# kulgurpowerMCU3.net
KiCad netlist of a schematic drawn in EAGLE
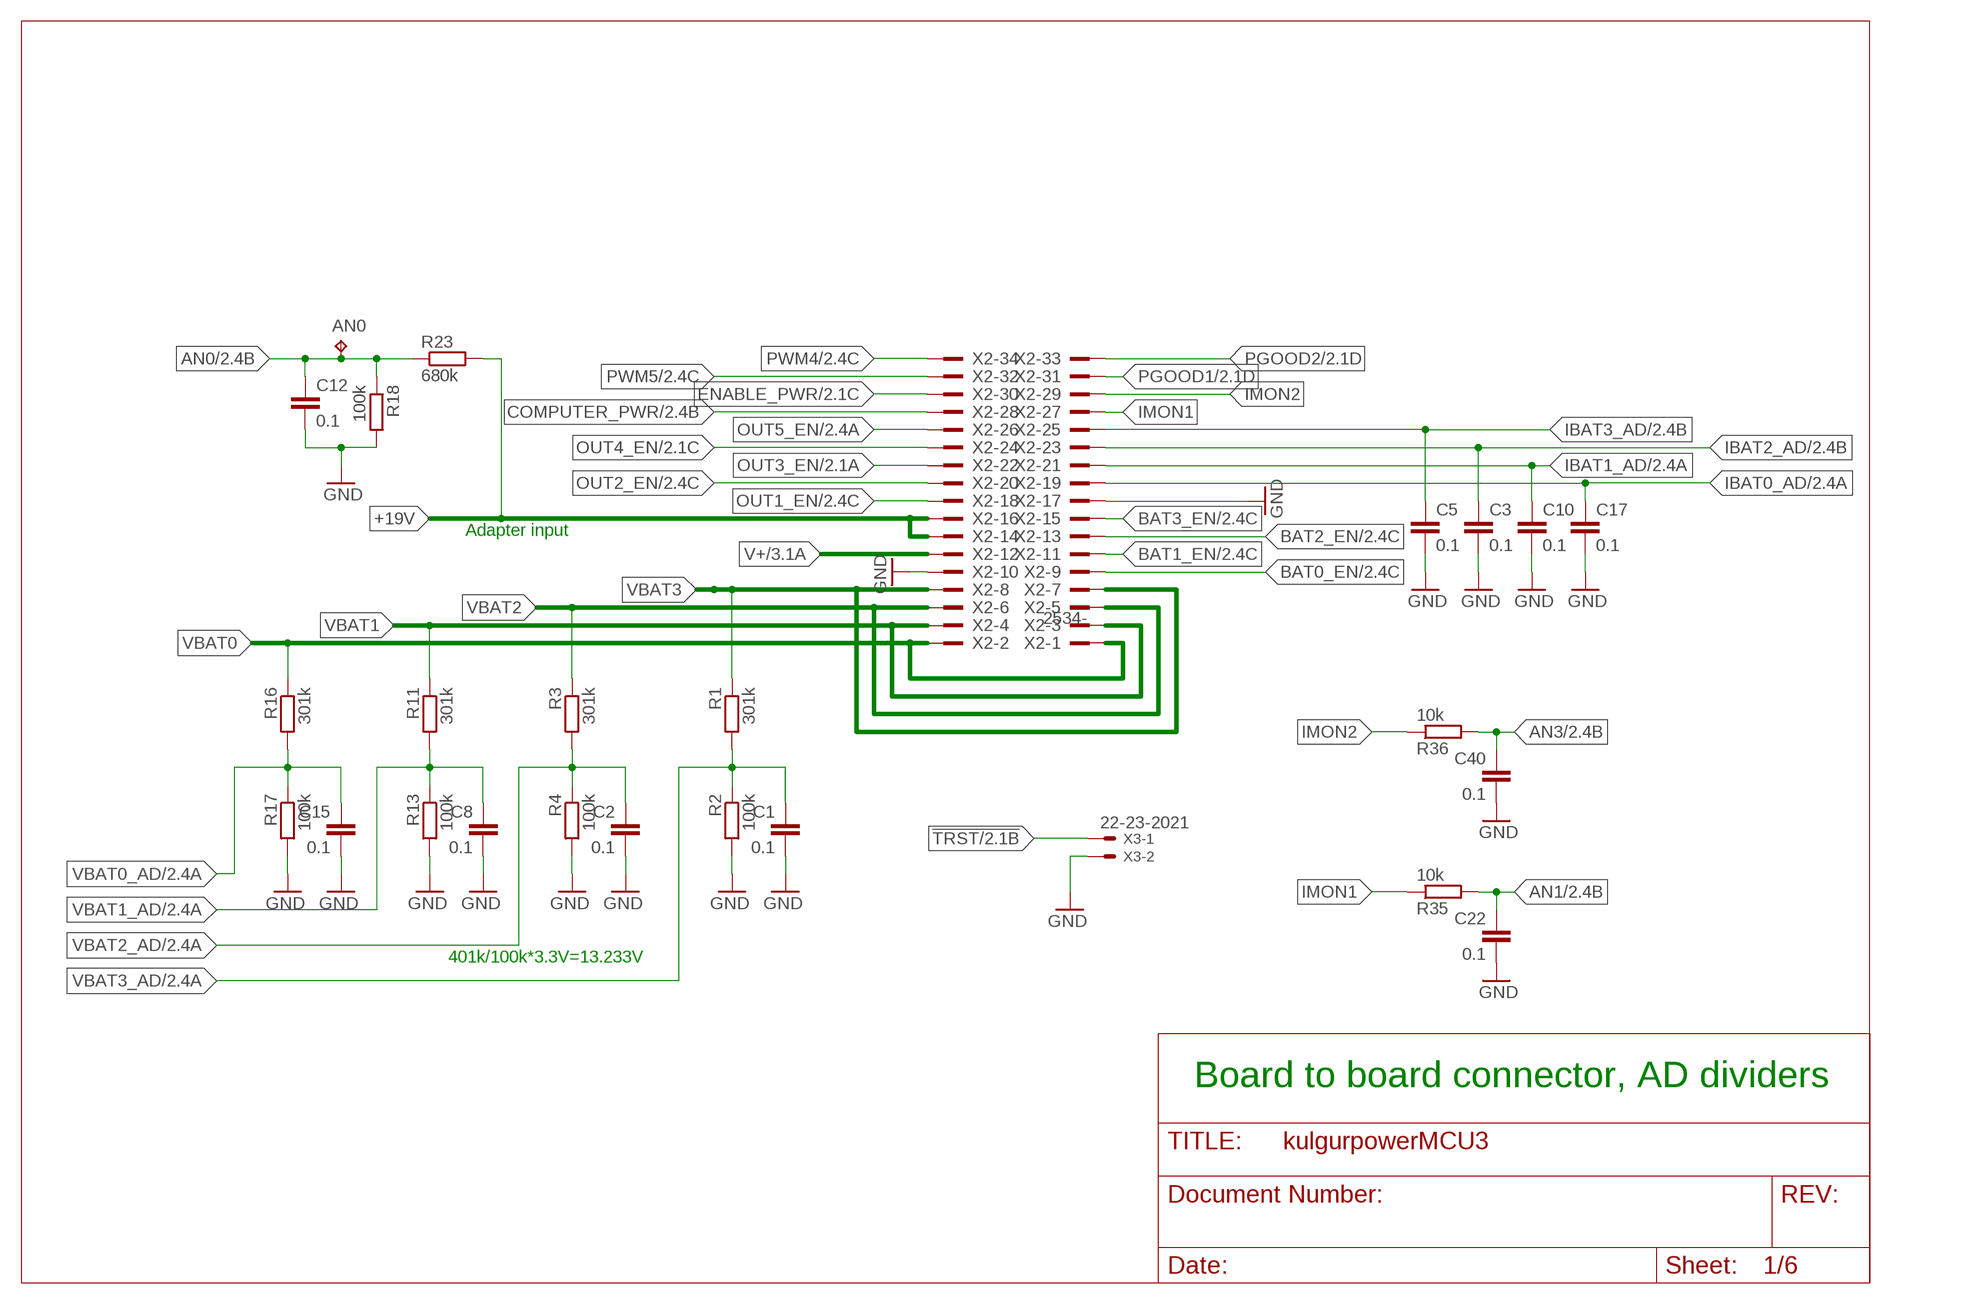
[diagram p0: schematic, sheet 1]
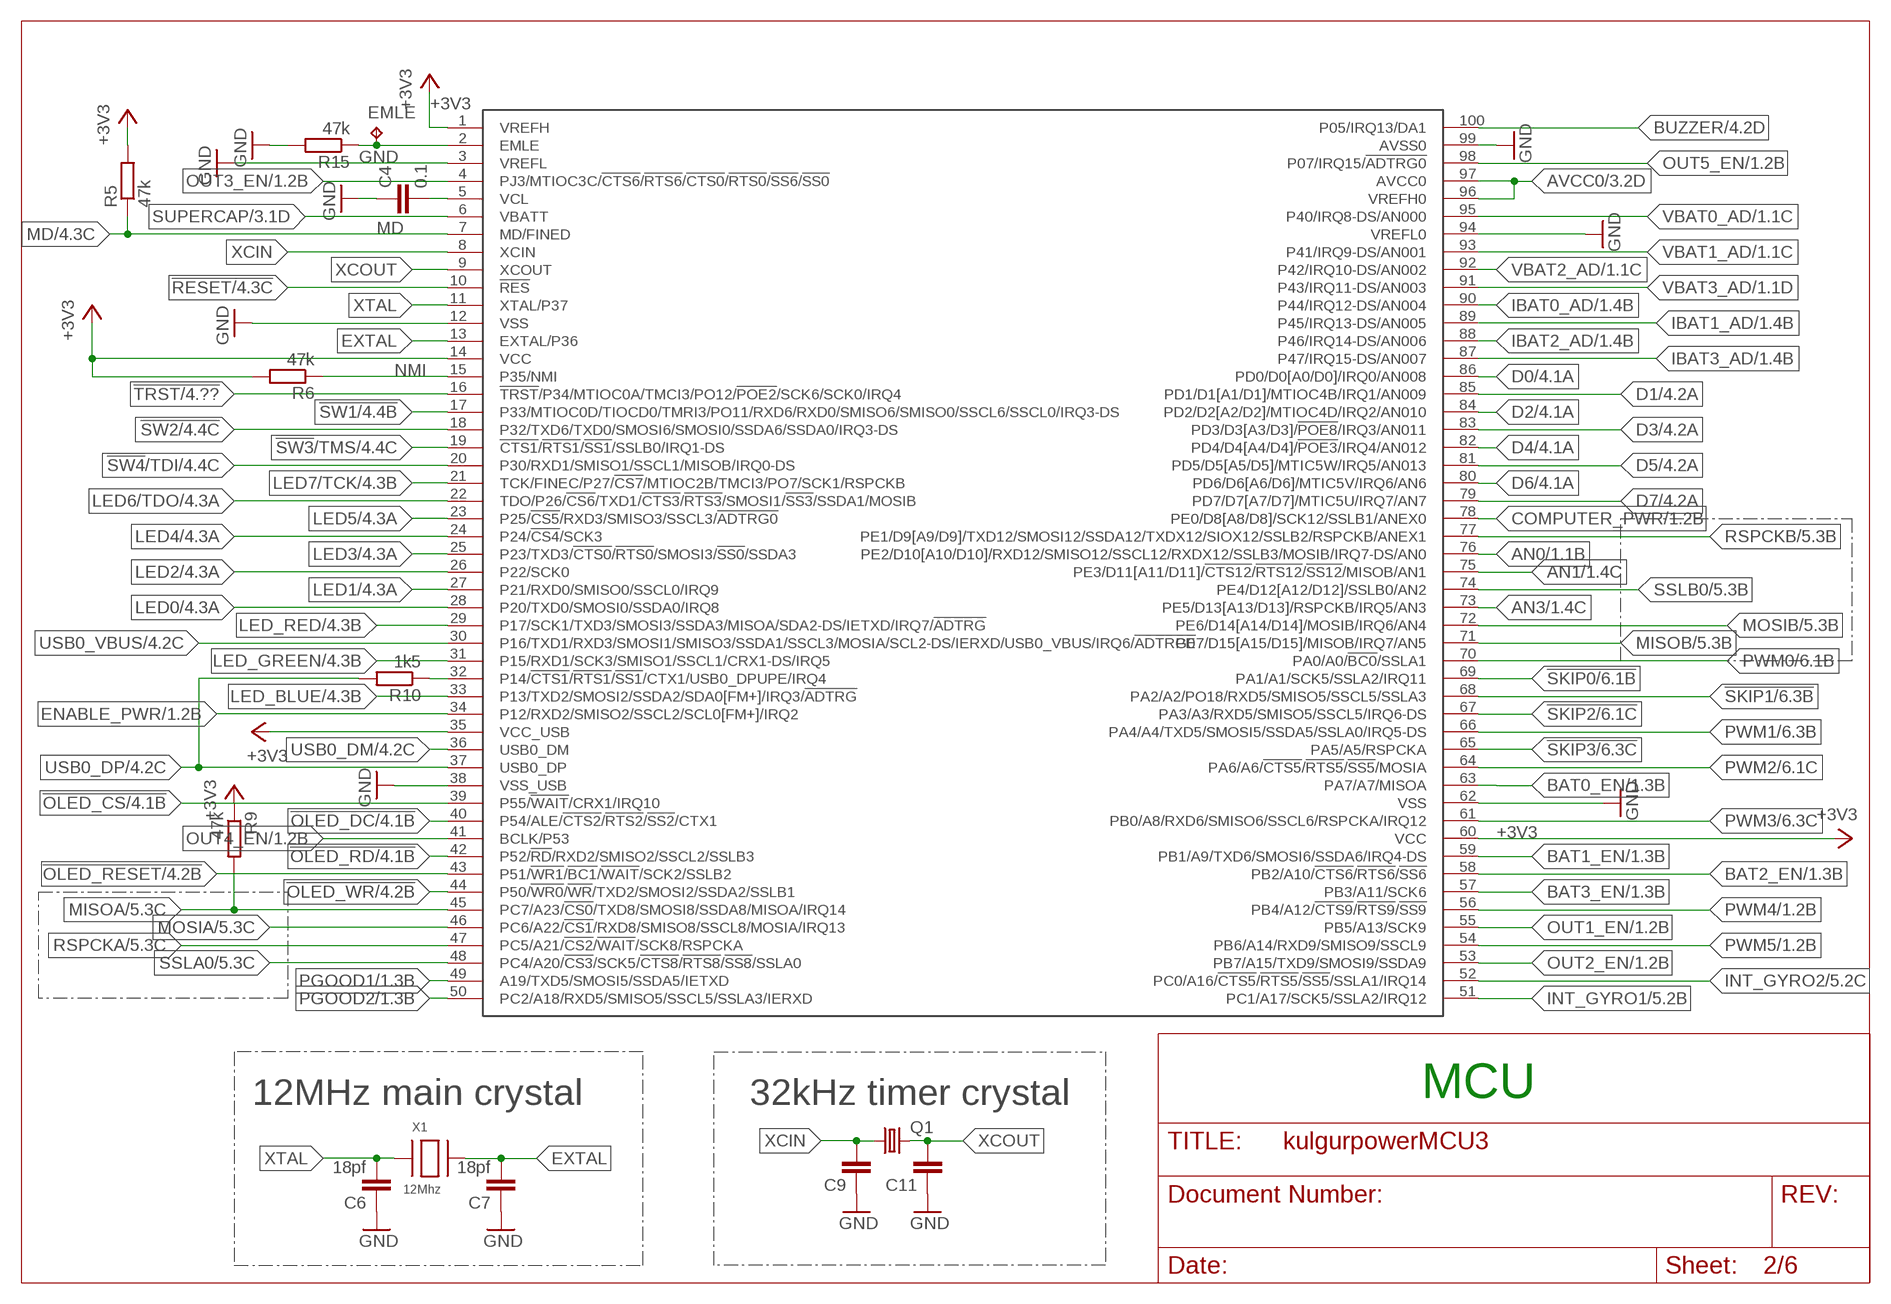
[diagram p1: schematic, sheet 2]
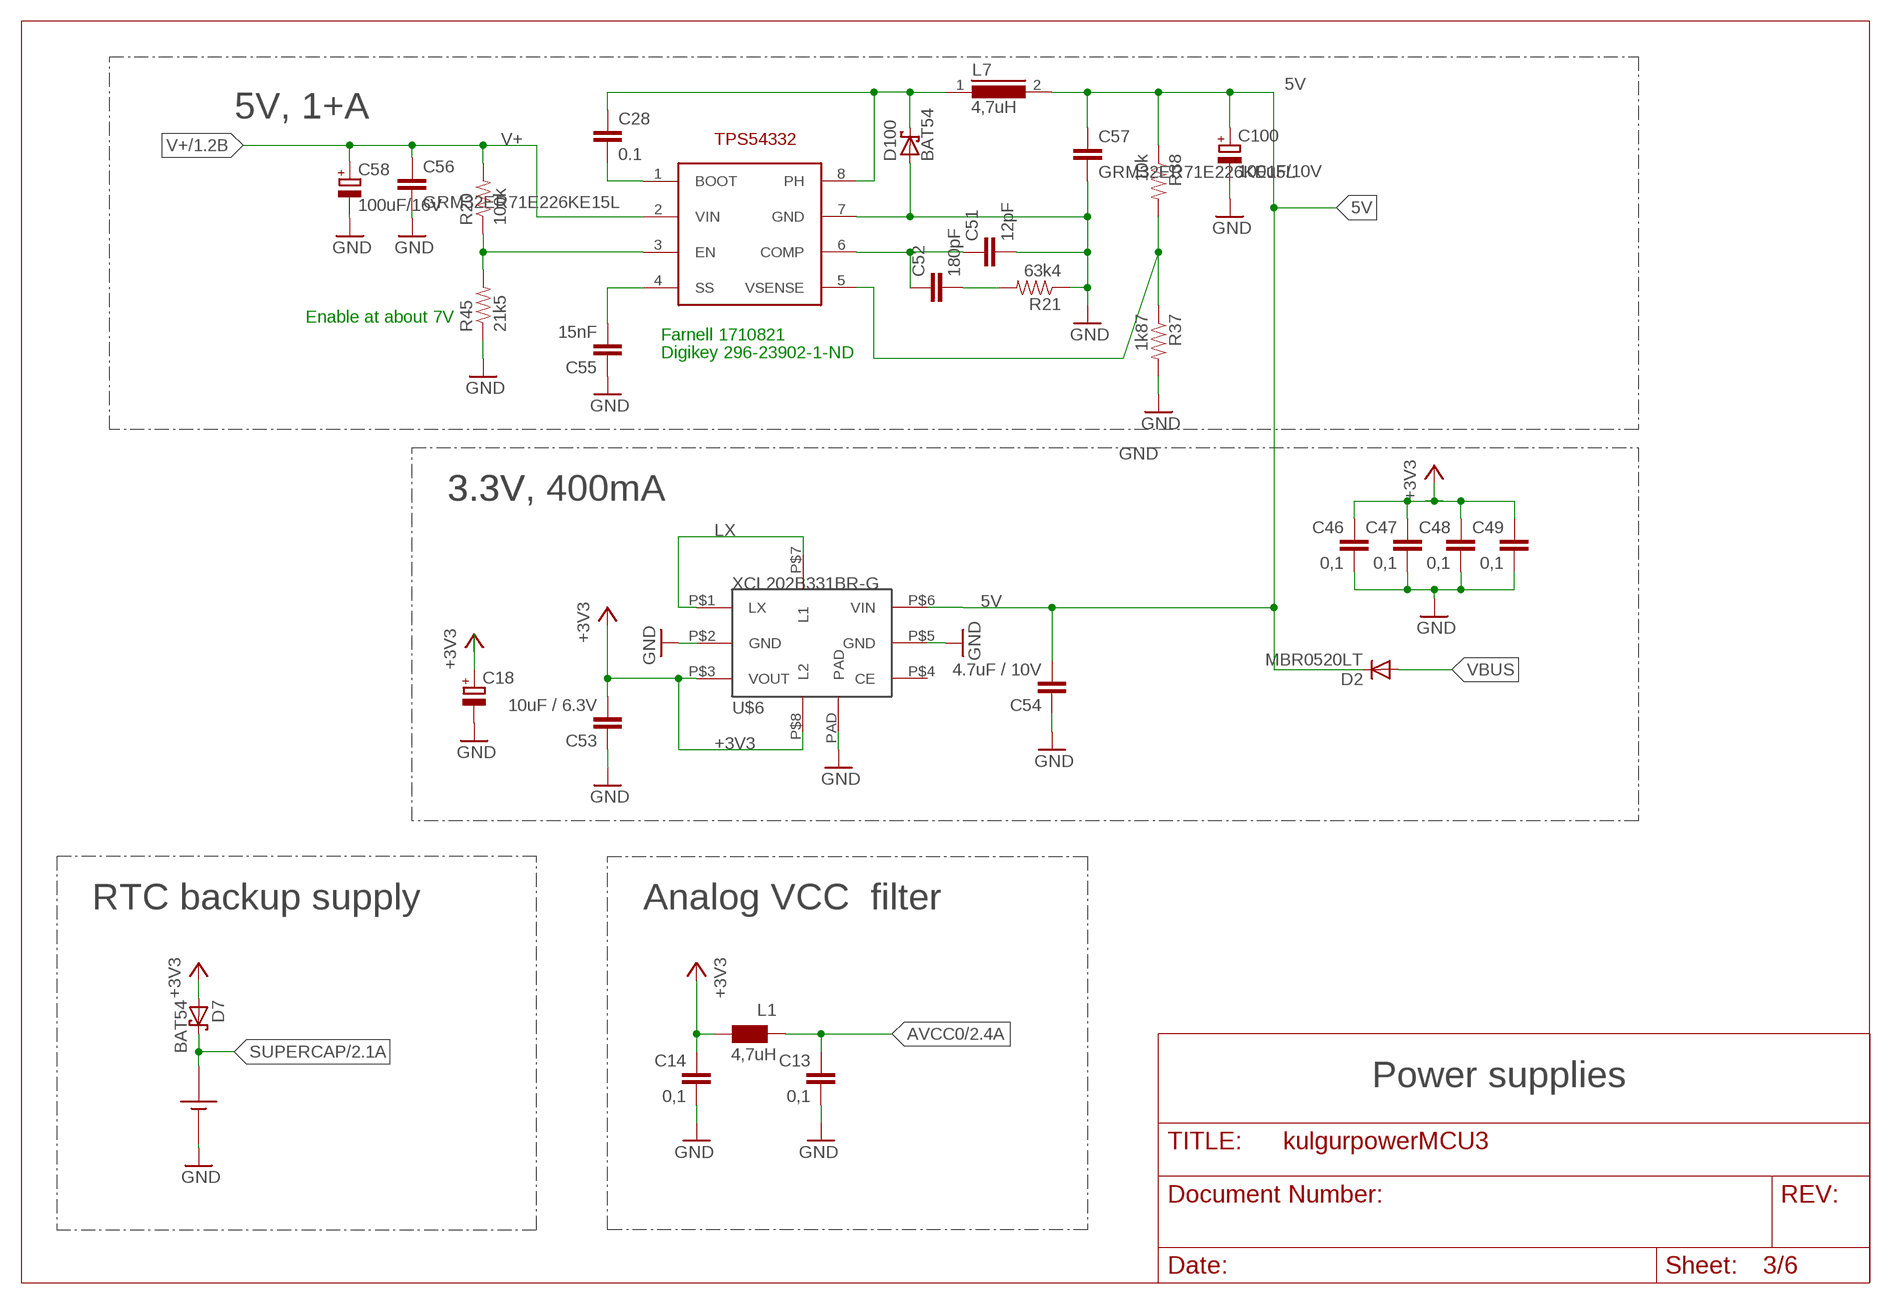
[diagram p2: schematic, sheet 3]
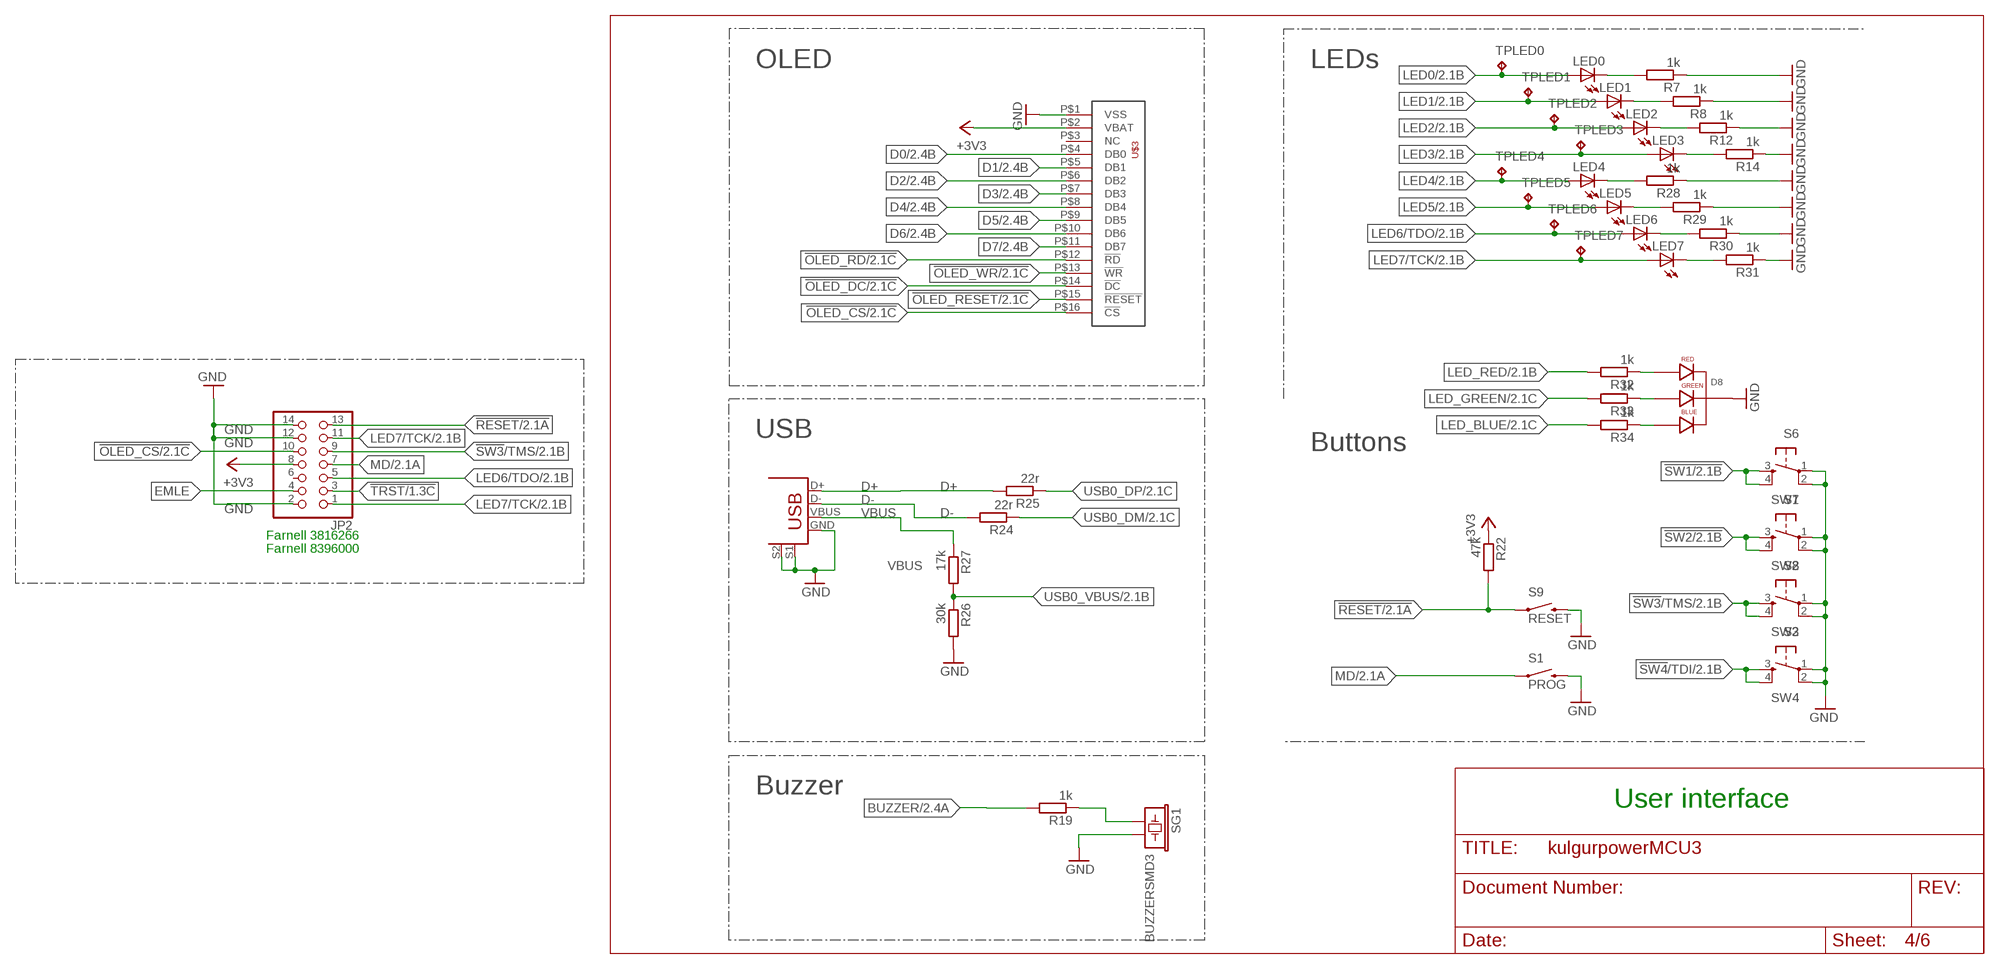
[diagram p3: schematic, sheet 4]
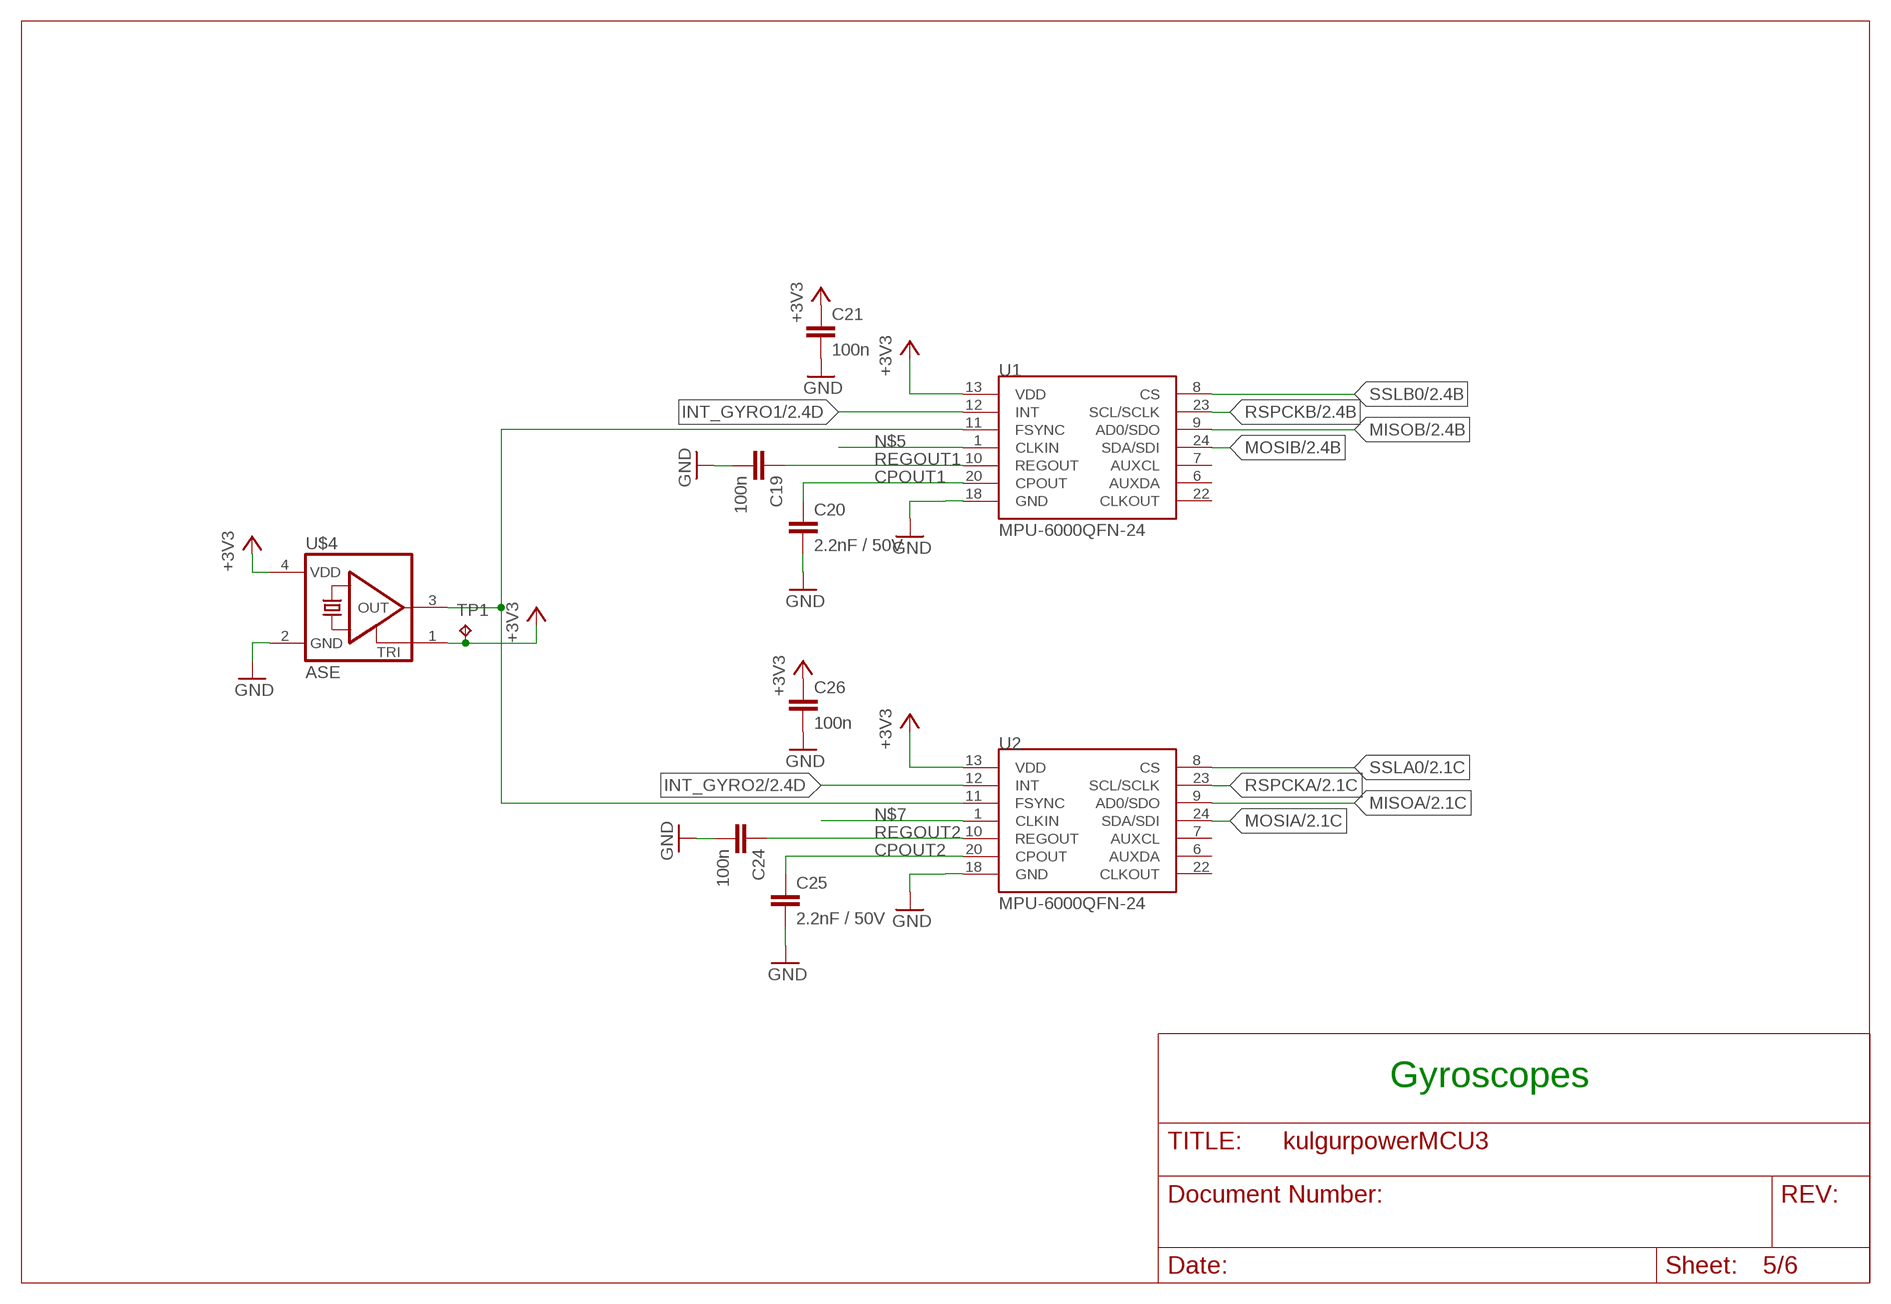
[diagram p4: schematic, sheet 5]
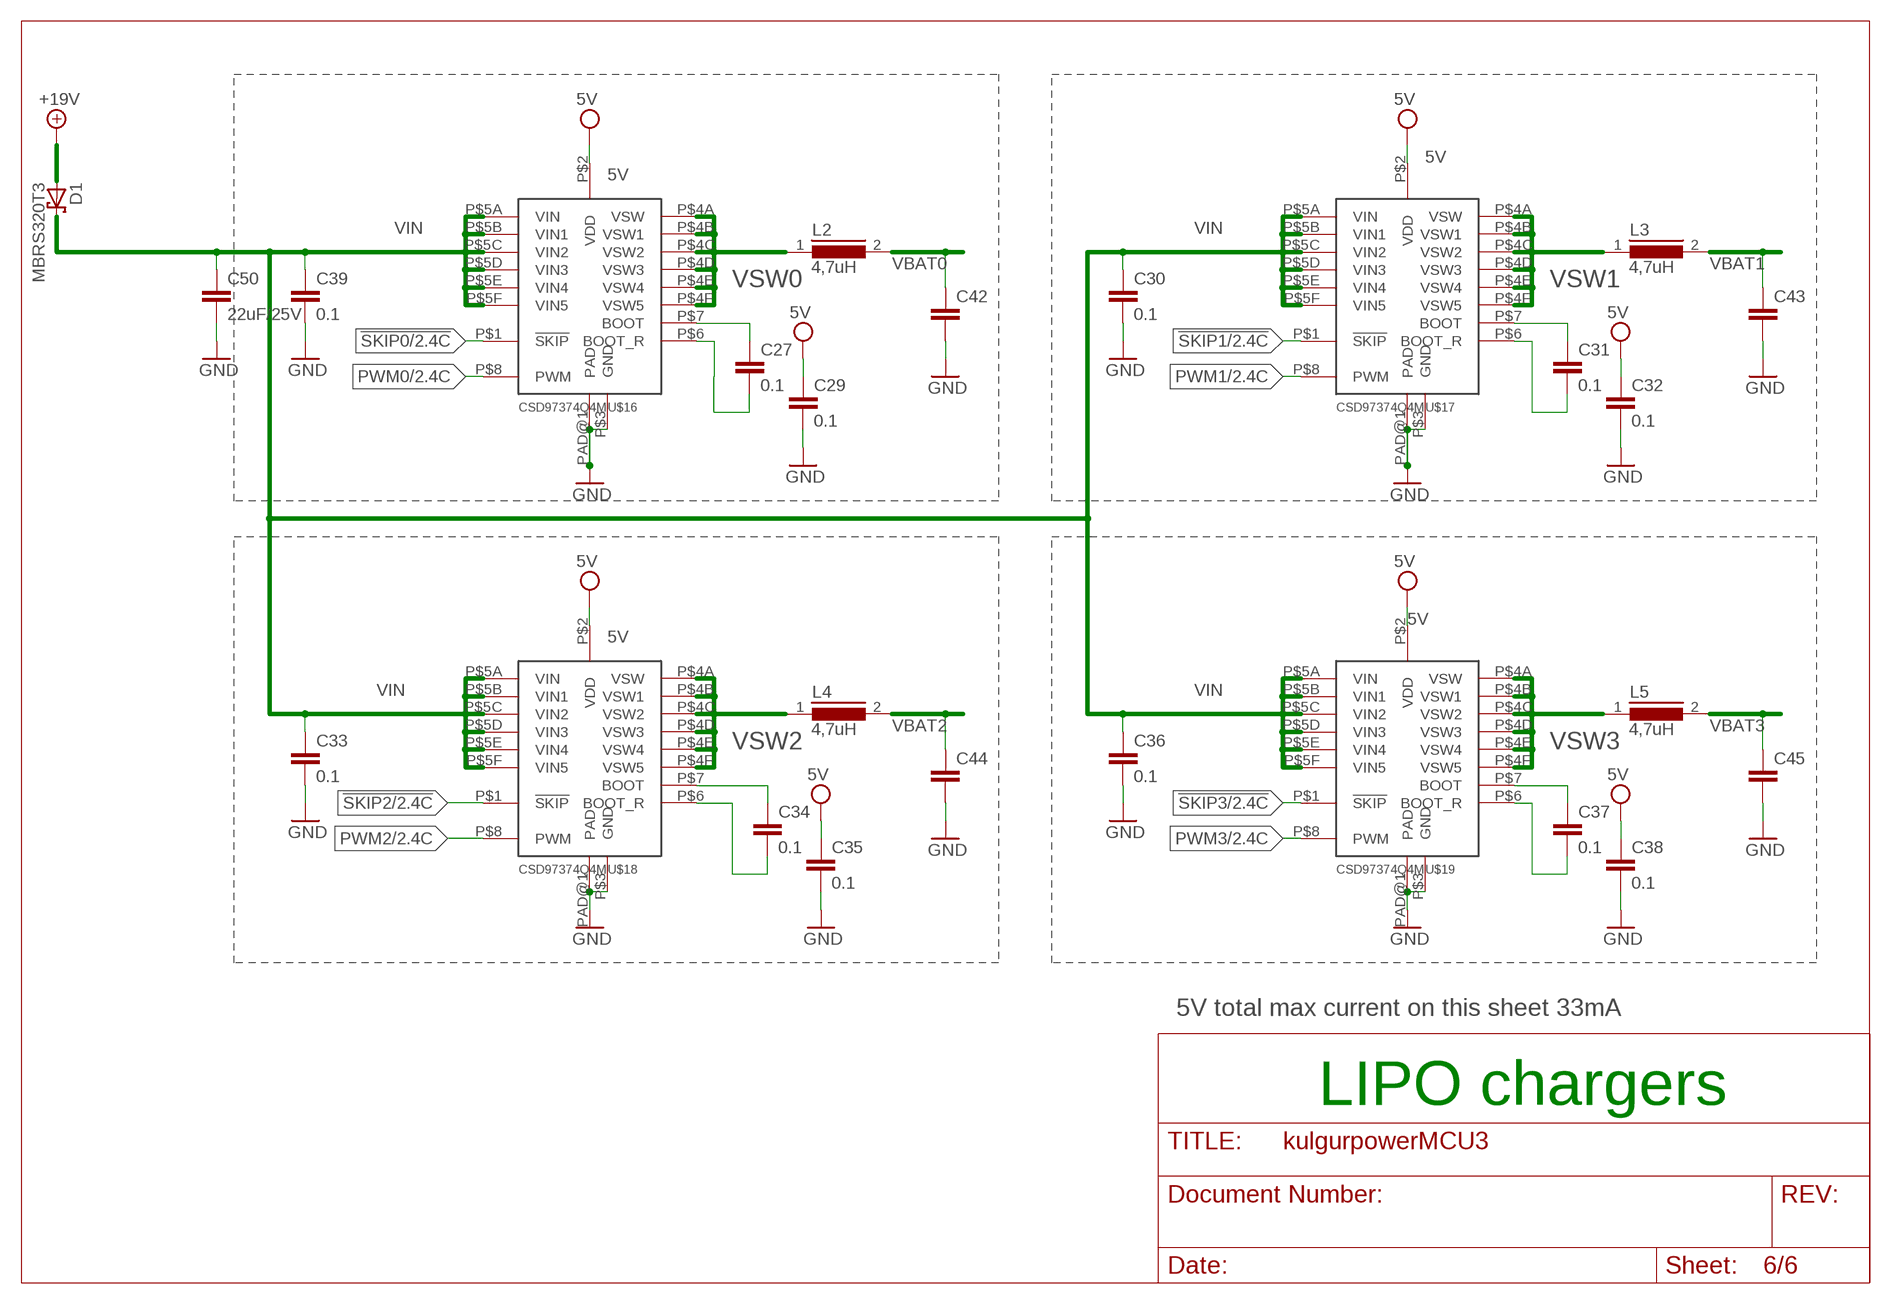
[diagram p5: schematic, sheet 6]

(export (version "E")
  (design (tool "Eeschema 10.0.6"))
  (components
    (comp (ref "D8")
      (value "WP154A4SUREQBFZGW")
      (footprint "eagle-import:LED-RGB-THRU")
      (fields (field (name "PROD_ID") "DIO-09434"))
      (libsource (lib "eagle-import") (part "LED-RGB-CC-THRUDIFFUSE"))
    )
    (comp (ref "JP2")
      (value "PINHD-2X7")
      (footprint "eagle-import:2X07")
      (libsource (lib "eagle-import") (part "PINHD-2X7"))
    )
    (comp (ref "LED0")
      (value "LED0603")
      (footprint "eagle-import:LED-0603")
      (libsource (lib "eagle-import") (part "LED0603"))
    )
    (comp (ref "LED1")
      (value "LED0603")
      (footprint "eagle-import:LED-0603")
      (libsource (lib "eagle-import") (part "LED0603"))
    )
    (comp (ref "LED2")
      (value "LED0603")
      (footprint "eagle-import:LED-0603")
      (libsource (lib "eagle-import") (part "LED0603"))
    )
    (comp (ref "LED3")
      (value "LED0603")
      (footprint "eagle-import:LED-0603")
      (libsource (lib "eagle-import") (part "LED0603"))
    )
    (comp (ref "LED4")
      (value "LED0603")
      (footprint "eagle-import:LED-0603")
      (libsource (lib "eagle-import") (part "LED0603"))
    )
    (comp (ref "LED5")
      (value "LED0603")
      (footprint "eagle-import:LED-0603")
      (libsource (lib "eagle-import") (part "LED0603"))
    )
    (comp (ref "LED6")
      (value "LED0603")
      (footprint "eagle-import:LED-0603")
      (libsource (lib "eagle-import") (part "LED0603"))
    )
    (comp (ref "LED7")
      (value "LED0603")
      (footprint "eagle-import:LED-0603")
      (libsource (lib "eagle-import") (part "LED0603"))
    )
    (comp (ref "R7")
      (value "1k")
      (footprint "eagle-import:R0603")
      (libsource (lib "eagle-import") (part "R-EU_R0603"))
    )
    (comp (ref "R8")
      (value "1k")
      (footprint "eagle-import:R0603")
      (libsource (lib "eagle-import") (part "R-EU_R0603"))
    )
    (comp (ref "R12")
      (value "1k")
      (footprint "eagle-import:R0603")
      (libsource (lib "eagle-import") (part "R-EU_R0603"))
    )
    (comp (ref "R14")
      (value "1k")
      (footprint "eagle-import:R0603")
      (libsource (lib "eagle-import") (part "R-EU_R0603"))
    )
    (comp (ref "R19")
      (value "1k")
      (footprint "eagle-import:R0603")
      (libsource (lib "eagle-import") (part "R-EU_R0603"))
    )
    (comp (ref "R22")
      (value "47k")
      (footprint "eagle-import:R0603")
      (libsource (lib "eagle-import") (part "R-EU_R0603"))
    )
    (comp (ref "R24")
      (value "22r")
      (footprint "eagle-import:R0603")
      (libsource (lib "eagle-import") (part "R-EU_R0603"))
    )
    (comp (ref "R25")
      (value "22r")
      (footprint "eagle-import:R0603")
      (libsource (lib "eagle-import") (part "R-EU_R0603"))
    )
    (comp (ref "R26")
      (value "30k")
      (footprint "eagle-import:R0603")
      (libsource (lib "eagle-import") (part "R-EU_R0603"))
    )
    (comp (ref "R27")
      (value "17k")
      (footprint "eagle-import:R0603")
      (libsource (lib "eagle-import") (part "R-EU_R0603"))
    )
    (comp (ref "R28")
      (value "1k")
      (footprint "eagle-import:R0603")
      (libsource (lib "eagle-import") (part "R-EU_R0603"))
    )
    (comp (ref "R29")
      (value "1k")
      (footprint "eagle-import:R0603")
      (libsource (lib "eagle-import") (part "R-EU_R0603"))
    )
    (comp (ref "R30")
      (value "1k")
      (footprint "eagle-import:R0603")
      (libsource (lib "eagle-import") (part "R-EU_R0603"))
    )
    (comp (ref "R31")
      (value "1k")
      (footprint "eagle-import:R0603")
      (libsource (lib "eagle-import") (part "R-EU_R0603"))
    )
    (comp (ref "R32")
      (value "1k")
      (footprint "eagle-import:R0603")
      (libsource (lib "eagle-import") (part "R-EU_R0603"))
    )
    (comp (ref "R33")
      (value "1k")
      (footprint "eagle-import:R0603")
      (libsource (lib "eagle-import") (part "R-EU_R0603"))
    )
    (comp (ref "R34")
      (value "1k")
      (footprint "eagle-import:R0603")
      (libsource (lib "eagle-import") (part "R-EU_R0603"))
    )
    (comp (ref "S1")
      (value "PROG")
      (footprint "eagle-import:TACTILE-PTH-SIDEEZ")
      (libsource (lib "eagle-import") (part "SWITCH-MOMENTARY-2SIDE_EZ"))
    )
    (comp (ref "S2")
      (value "SW4")
      (footprint "eagle-import:TACTILE-PTH")
      (libsource (lib "eagle-import") (part "TAC_SWITCHPTH"))
    )
    (comp (ref "S6")
      (value "SW1")
      (footprint "eagle-import:TACTILE-PTH")
      (libsource (lib "eagle-import") (part "TAC_SWITCHPTH"))
    )
    (comp (ref "S7")
      (value "SW2")
      (footprint "eagle-import:TACTILE-PTH")
      (libsource (lib "eagle-import") (part "TAC_SWITCHPTH"))
    )
    (comp (ref "S8")
      (value "SW3")
      (footprint "eagle-import:TACTILE-PTH")
      (libsource (lib "eagle-import") (part "TAC_SWITCHPTH"))
    )
    (comp (ref "S9")
      (value "RESET")
      (footprint "eagle-import:TACTILE-PTH-SIDEEZ")
      (libsource (lib "eagle-import") (part "SWITCH-MOMENTARY-2SIDE_EZ"))
    )
    (comp (ref "SG1")
      (value "BUZZERSMD3")
      (footprint "eagle-import:BUZZER-CMT1102")
      (libsource (lib "eagle-import") (part "BUZZERSMD3"))
    )
    (comp (ref "TPLED0")
      (value "LED0")
      (footprint "eagle-import:B1,27")
      (libsource (lib "eagle-import") (part "TPB1,27"))
    )
    (comp (ref "TPLED1")
      (value "LED0")
      (footprint "eagle-import:B1,27")
      (libsource (lib "eagle-import") (part "TPB1,27"))
    )
    (comp (ref "TPLED2")
      (value "LED0")
      (footprint "eagle-import:B1,27")
      (libsource (lib "eagle-import") (part "TPB1,27"))
    )
    (comp (ref "TPLED3")
      (value "LED0")
      (footprint "eagle-import:B1,27")
      (libsource (lib "eagle-import") (part "TPB1,27"))
    )
    (comp (ref "TPLED4")
      (value "LED0")
      (footprint "eagle-import:B1,27")
      (libsource (lib "eagle-import") (part "TPB1,27"))
    )
    (comp (ref "TPLED5")
      (value "LED0")
      (footprint "eagle-import:B1,27")
      (libsource (lib "eagle-import") (part "TPB1,27"))
    )
    (comp (ref "TPLED6")
      (value "LED0")
      (footprint "eagle-import:B1,27")
      (libsource (lib "eagle-import") (part "TPB1,27"))
    )
    (comp (ref "TPLED7")
      (value "LED0")
      (footprint "eagle-import:B1,27")
      (libsource (lib "eagle-import") (part "TPB1,27"))
    )
    (comp (ref "U$2")
      (value "USB+SHIELD")
      (footprint "eagle-import:USB-B-PTH")
      (libsource (lib "eagle-import") (part "USB+SHIELD"))
    )
    (comp (ref "U$3")
      (value "ER-OLEDM032-1")
      (footprint "eagle-import:ER-OLEDM032-1")
      (libsource (lib "eagle-import") (part "ER-OLEDM032-1"))
    )
    (comp (ref "C4")
      (value "0.1")
      (footprint "eagle-import:0603-CAP")
      (libsource (lib "eagle-import") (part "CAP0603-CAP"))
    )
    (comp (ref "C6")
      (value "18pf")
      (footprint "eagle-import:0603-CAP")
      (libsource (lib "eagle-import") (part "CAP0603-CAP"))
    )
    (comp (ref "C7")
      (value "18pf")
      (footprint "eagle-import:0603-CAP")
      (libsource (lib "eagle-import") (part "CAP0603-CAP"))
    )
    (comp (ref "C9")
      (value "CAP0603-CAP")
      (footprint "eagle-import:0603-CAP")
      (libsource (lib "eagle-import") (part "CAP0603-CAP"))
    )
    (comp (ref "C11")
      (value "CAP0603-CAP")
      (footprint "eagle-import:0603-CAP")
      (libsource (lib "eagle-import") (part "CAP0603-CAP"))
    )
    (comp (ref "EMLE")
      (value "TPB1,27")
      (footprint "eagle-import:B1,27")
      (libsource (lib "eagle-import") (part "TPB1,27"))
    )
    (comp (ref "Q1")
      (value "CRYSTALMM20SS")
      (footprint "eagle-import:MM20SS")
      (libsource (lib "eagle-import") (part "CRYSTALMM20SS"))
    )
    (comp (ref "R5")
      (value "47k")
      (footprint "eagle-import:R0603")
      (libsource (lib "eagle-import") (part "R-EU_R0603"))
    )
    (comp (ref "R6")
      (value "47k")
      (footprint "eagle-import:R0603")
      (libsource (lib "eagle-import") (part "R-EU_R0603"))
    )
    (comp (ref "R9")
      (value "47k")
      (footprint "eagle-import:R0603")
      (libsource (lib "eagle-import") (part "R-EU_R0603"))
    )
    (comp (ref "R10")
      (value "1k5")
      (footprint "eagle-import:R0603")
      (libsource (lib "eagle-import") (part "R-EU_R0603"))
    )
    (comp (ref "R15")
      (value "47k")
      (footprint "eagle-import:R0603")
      (libsource (lib "eagle-import") (part "R-EU_R0603"))
    )
    (comp (ref "U$14")
      (value "R5F5630ADDFP")
      (footprint "eagle-import:LTQFP100")
      (libsource (lib "eagle-import") (part "R5F5630ADDFP"))
    )
    (comp (ref "X1")
      (value "12Mhz")
      (footprint "eagle-import:NX5032")
      (libsource (lib "eagle-import") (part "XTALNX5032"))
    )
    (comp (ref "C27")
      (value "0.1")
      (footprint "eagle-import:C0603")
      (libsource (lib "eagle-import") (part "C-EUC0603"))
    )
    (comp (ref "C29")
      (value "0.1")
      (footprint "eagle-import:C0603")
      (libsource (lib "eagle-import") (part "C-EUC0603"))
    )
    (comp (ref "C30")
      (value "0.1")
      (footprint "eagle-import:C1210")
      (libsource (lib "eagle-import") (part "C-EUC1210"))
    )
    (comp (ref "C31")
      (value "0.1")
      (footprint "eagle-import:C0603")
      (libsource (lib "eagle-import") (part "C-EUC0603"))
    )
    (comp (ref "C32")
      (value "0.1")
      (footprint "eagle-import:C0603")
      (libsource (lib "eagle-import") (part "C-EUC0603"))
    )
    (comp (ref "C33")
      (value "0.1")
      (footprint "eagle-import:C1210")
      (libsource (lib "eagle-import") (part "C-EUC1210"))
    )
    (comp (ref "C34")
      (value "0.1")
      (footprint "eagle-import:C0603")
      (libsource (lib "eagle-import") (part "C-EUC0603"))
    )
    (comp (ref "C35")
      (value "0.1")
      (footprint "eagle-import:C0603")
      (libsource (lib "eagle-import") (part "C-EUC0603"))
    )
    (comp (ref "C36")
      (value "0.1")
      (footprint "eagle-import:C1210")
      (libsource (lib "eagle-import") (part "C-EUC1210"))
    )
    (comp (ref "C37")
      (value "0.1")
      (footprint "eagle-import:C0603")
      (libsource (lib "eagle-import") (part "C-EUC0603"))
    )
    (comp (ref "C38")
      (value "0.1")
      (footprint "eagle-import:C0603")
      (libsource (lib "eagle-import") (part "C-EUC0603"))
    )
    (comp (ref "C39")
      (value "0.1")
      (footprint "eagle-import:C1210")
      (libsource (lib "eagle-import") (part "C-EUC1210"))
    )
    (comp (ref "C42")
      (value "C-EUC1210")
      (footprint "eagle-import:C1210")
      (libsource (lib "eagle-import") (part "C-EUC1210"))
    )
    (comp (ref "C43")
      (value "C-EUC1210")
      (footprint "eagle-import:C1210")
      (libsource (lib "eagle-import") (part "C-EUC1210"))
    )
    (comp (ref "C44")
      (value "C-EUC1210")
      (footprint "eagle-import:C1210")
      (libsource (lib "eagle-import") (part "C-EUC1210"))
    )
    (comp (ref "C45")
      (value "C-EUC1210")
      (footprint "eagle-import:C1210")
      (libsource (lib "eagle-import") (part "C-EUC1210"))
    )
    (comp (ref "C50")
      (value "22uF/25V")
      (footprint "eagle-import:C1210")
      (libsource (lib "eagle-import") (part "C-EUC1210"))
    )
    (comp (ref "D1")
      (value "MBRS320T3")
      (footprint "eagle-import:SMC")
      (libsource (lib "eagle-import") (part "MBRS30T32"))
    )
    (comp (ref "L2")
      (value "4,7uH")
      (footprint "eagle-import:DR73")
      (libsource (lib "eagle-import") (part "DR73"))
    )
    (comp (ref "L3")
      (value "4,7uH")
      (footprint "eagle-import:DR73")
      (libsource (lib "eagle-import") (part "DR73"))
    )
    (comp (ref "L4")
      (value "4,7uH")
      (footprint "eagle-import:DR73")
      (libsource (lib "eagle-import") (part "DR73"))
    )
    (comp (ref "L5")
      (value "4,7uH")
      (footprint "eagle-import:DR73")
      (libsource (lib "eagle-import") (part "DR73"))
    )
    (comp (ref "U$16")
      (value "CSD97374Q4M")
      (footprint "eagle-import:CSD97374Q4M")
      (libsource (lib "eagle-import") (part "CSD97374Q4M"))
    )
    (comp (ref "U$17")
      (value "CSD97374Q4M")
      (footprint "eagle-import:CSD97374Q4M")
      (libsource (lib "eagle-import") (part "CSD97374Q4M"))
    )
    (comp (ref "U$18")
      (value "CSD97374Q4M")
      (footprint "eagle-import:CSD97374Q4M")
      (libsource (lib "eagle-import") (part "CSD97374Q4M"))
    )
    (comp (ref "U$19")
      (value "CSD97374Q4M")
      (footprint "eagle-import:CSD97374Q4M")
      (libsource (lib "eagle-import") (part "CSD97374Q4M"))
    )
    (comp (ref "C13")
      (value "0,1")
      (footprint "eagle-import:0603-CAP")
      (libsource (lib "eagle-import") (part "CAP0603-CAP"))
    )
    (comp (ref "C14")
      (value "0,1")
      (footprint "eagle-import:0603-CAP")
      (libsource (lib "eagle-import") (part "CAP0603-CAP"))
    )
    (comp (ref "C18")
      (value "CPOL-EUC/6032-28R")
      (footprint "eagle-import:C_6032-28R")
      (libsource (lib "eagle-import") (part "CPOL-EUC/6032-28R"))
    )
    (comp (ref "C28")
      (value "0.1")
      (footprint "eagle-import:0603-CAP")
      (libsource (lib "eagle-import") (part "CAP0603-CAP"))
    )
    (comp (ref "C46")
      (value "0,1")
      (footprint "eagle-import:0603-CAP")
      (libsource (lib "eagle-import") (part "CAP0603-CAP"))
    )
    (comp (ref "C47")
      (value "0,1")
      (footprint "eagle-import:0603-CAP")
      (libsource (lib "eagle-import") (part "CAP0603-CAP"))
    )
    (comp (ref "C48")
      (value "0,1")
      (footprint "eagle-import:0603-CAP")
      (libsource (lib "eagle-import") (part "CAP0603-CAP"))
    )
    (comp (ref "C49")
      (value "0,1")
      (footprint "eagle-import:0603-CAP")
      (libsource (lib "eagle-import") (part "CAP0603-CAP"))
    )
    (comp (ref "C51")
      (value "12pF")
      (footprint "eagle-import:0603-CAP")
      (libsource (lib "eagle-import") (part "CAP0603-CAP"))
    )
    (comp (ref "C52")
      (value "180pF")
      (footprint "eagle-import:0603-CAP")
      (libsource (lib "eagle-import") (part "CAP0603-CAP"))
    )
    (comp (ref "C53")
      (value "10uF / 6.3V")
      (footprint "eagle-import:C0603")
      (libsource (lib "eagle-import") (part "C-EUC0603"))
    )
    (comp (ref "C54")
      (value "4.7uF / 10V")
      (footprint "eagle-import:C0603")
      (libsource (lib "eagle-import") (part "C-EUC0603"))
    )
    (comp (ref "C55")
      (value "15nF")
      (footprint "eagle-import:0603-CAP")
      (libsource (lib "eagle-import") (part "CAP0603-CAP"))
    )
    (comp (ref "C56")
      (value "GRM32ER71E226KE15L")
      (footprint "eagle-import:C1210")
      (libsource (lib "eagle-import") (part "C-EUC1210"))
    )
    (comp (ref "C57")
      (value "GRM32ER71E226KE15L")
      (footprint "eagle-import:C1210")
      (libsource (lib "eagle-import") (part "C-EUC1210"))
    )
    (comp (ref "C58")
      (value "100uF/16V")
      (footprint "eagle-import:C_6032-28R")
      (libsource (lib "eagle-import") (part "CPOL-EUC/6032-28R"))
    )
    (comp (ref "C100")
      (value "100uF/10V")
      (footprint "eagle-import:C_6032-28R")
      (libsource (lib "eagle-import") (part "CPOL-EUC/6032-28R"))
    )
    (comp (ref "D2")
      (value "MBR0520LT")
      (footprint "eagle-import:SOD123")
      (libsource (lib "eagle-import") (part "MBR0520LT"))
    )
    (comp (ref "D7")
      (value "BAT54")
      (footprint "eagle-import:SOT23")
      (libsource (lib "eagle-import") (part "BAT54"))
    )
    (comp (ref "D100")
      (value "BAT54")
      (footprint "eagle-import:SOT23")
      (libsource (lib "eagle-import") (part "BAT54"))
    )
    (comp (ref "L1")
      (value "4,7uH")
      (footprint "eagle-import:WE-KI_0805_B")
      (libsource (lib "eagle-import") (part "WE-KIHQ_0805"))
    )
    (comp (ref "L7")
      (value "4,7uH")
      (footprint "eagle-import:DR73")
      (libsource (lib "eagle-import") (part "DR73"))
    )
    (comp (ref "R20")
      (value "100k")
      (footprint "eagle-import:0603-RES")
      (libsource (lib "eagle-import") (part "RESISTOR0603-RES"))
    )
    (comp (ref "R21")
      (value "63k4")
      (footprint "eagle-import:0603-RES")
      (libsource (lib "eagle-import") (part "RESISTOR0603-RES"))
    )
    (comp (ref "R37")
      (value "1k87")
      (footprint "eagle-import:0603-RES")
      (libsource (lib "eagle-import") (part "RESISTOR0603-RES"))
    )
    (comp (ref "R38")
      (value "10k")
      (footprint "eagle-import:0603-RES")
      (libsource (lib "eagle-import") (part "RESISTOR0603-RES"))
    )
    (comp (ref "R45")
      (value "21k5")
      (footprint "eagle-import:0603-RES")
      (libsource (lib "eagle-import") (part "RESISTOR0603-RES"))
    )
    (comp (ref "U$1")
      (value "EDLRD224V3R6C")
      (footprint "eagle-import:EDLRD224V3R6C")
      (libsource (lib "eagle-import") (part "EDLRD224V3R6C"))
    )
    (comp (ref "U$5")
      (value "TPS54332")
      (footprint "eagle-import:SO8")
      (libsource (lib "eagle-import") (part "TPS54332"))
    )
    (comp (ref "U$6")
      (value "XCL202B331BR-G")
      (footprint "eagle-import:CL2025")
      (libsource (lib "eagle-import") (part "XCL202"))
    )
    (comp (ref "AN0")
      (value "TPB1,27")
      (footprint "eagle-import:B1,27")
      (libsource (lib "eagle-import") (part "TPB1,27"))
    )
    (comp (ref "C1")
      (value "0.1")
      (footprint "eagle-import:C0603")
      (libsource (lib "eagle-import") (part "C-EUC0603"))
    )
    (comp (ref "C2")
      (value "0.1")
      (footprint "eagle-import:C0603")
      (libsource (lib "eagle-import") (part "C-EUC0603"))
    )
    (comp (ref "C3")
      (value "0.1")
      (footprint "eagle-import:C0603")
      (libsource (lib "eagle-import") (part "C-EUC0603"))
    )
    (comp (ref "C5")
      (value "0.1")
      (footprint "eagle-import:C0603")
      (libsource (lib "eagle-import") (part "C-EUC0603"))
    )
    (comp (ref "C8")
      (value "0.1")
      (footprint "eagle-import:C0603")
      (libsource (lib "eagle-import") (part "C-EUC0603"))
    )
    (comp (ref "C10")
      (value "0.1")
      (footprint "eagle-import:C0603")
      (libsource (lib "eagle-import") (part "C-EUC0603"))
    )
    (comp (ref "C12")
      (value "0.1")
      (footprint "eagle-import:0603-CAP")
      (libsource (lib "eagle-import") (part "CAP0603-CAP"))
    )
    (comp (ref "C15")
      (value "0.1")
      (footprint "eagle-import:C0603")
      (libsource (lib "eagle-import") (part "C-EUC0603"))
    )
    (comp (ref "C17")
      (value "0.1")
      (footprint "eagle-import:C0603")
      (libsource (lib "eagle-import") (part "C-EUC0603"))
    )
    (comp (ref "C22")
      (value "0.1")
      (footprint "eagle-import:C0603")
      (libsource (lib "eagle-import") (part "C-EUC0603"))
    )
    (comp (ref "C40")
      (value "0.1")
      (footprint "eagle-import:C0603")
      (libsource (lib "eagle-import") (part "C-EUC0603"))
    )
    (comp (ref "R1")
      (value "301k")
      (footprint "eagle-import:R0603")
      (libsource (lib "eagle-import") (part "R-EU_R0603"))
    )
    (comp (ref "R2")
      (value "100k")
      (footprint "eagle-import:R0603")
      (libsource (lib "eagle-import") (part "R-EU_R0603"))
    )
    (comp (ref "R3")
      (value "301k")
      (footprint "eagle-import:R0603")
      (libsource (lib "eagle-import") (part "R-EU_R0603"))
    )
    (comp (ref "R4")
      (value "100k")
      (footprint "eagle-import:R0603")
      (libsource (lib "eagle-import") (part "R-EU_R0603"))
    )
    (comp (ref "R11")
      (value "301k")
      (footprint "eagle-import:R0603")
      (libsource (lib "eagle-import") (part "R-EU_R0603"))
    )
    (comp (ref "R13")
      (value "100k")
      (footprint "eagle-import:R0603")
      (libsource (lib "eagle-import") (part "R-EU_R0603"))
    )
    (comp (ref "R16")
      (value "301k")
      (footprint "eagle-import:R0603")
      (libsource (lib "eagle-import") (part "R-EU_R0603"))
    )
    (comp (ref "R17")
      (value "100k")
      (footprint "eagle-import:R0603")
      (libsource (lib "eagle-import") (part "R-EU_R0603"))
    )
    (comp (ref "R18")
      (value "100k")
      (footprint "eagle-import:R0603")
      (libsource (lib "eagle-import") (part "R-EU_R0603"))
    )
    (comp (ref "R23")
      (value "680k")
      (footprint "eagle-import:R0603")
      (libsource (lib "eagle-import") (part "R-EU_R0603"))
    )
    (comp (ref "R35")
      (value "10k")
      (footprint "eagle-import:R0603")
      (libsource (lib "eagle-import") (part "R-EU_R0603"))
    )
    (comp (ref "R36")
      (value "10k")
      (footprint "eagle-import:R0603")
      (libsource (lib "eagle-import") (part "R-EU_R0603"))
    )
    (comp (ref "X2")
      (value "2534-")
      (footprint "eagle-import:PAK100_2500-34")
      (libsource (lib "eagle-import") (part "2534-"))
    )
    (comp (ref "X3")
      (value "22-23-2021")
      (footprint "eagle-import:22-23-2021")
      (fields (field (name "MF") "MOLEX"))
      (libsource (lib "eagle-import") (part "22-23-2021"))
    )
    (comp (ref "C19")
      (value "100n")
      (footprint "eagle-import:C0603")
      (libsource (lib "eagle-import") (part "C-EUC0603"))
    )
    (comp (ref "C20")
      (value "2.2nF / 50V")
      (footprint "eagle-import:C0402")
      (libsource (lib "eagle-import") (part "C0402"))
    )
    (comp (ref "C21")
      (value "100n")
      (footprint "eagle-import:C0603")
      (libsource (lib "eagle-import") (part "C-EUC0603"))
    )
    (comp (ref "C24")
      (value "100n")
      (footprint "eagle-import:C0603")
      (libsource (lib "eagle-import") (part "C-EUC0603"))
    )
    (comp (ref "C25")
      (value "2.2nF / 50V")
      (footprint "eagle-import:C0402")
      (libsource (lib "eagle-import") (part "C0402"))
    )
    (comp (ref "C26")
      (value "100n")
      (footprint "eagle-import:C0603")
      (libsource (lib "eagle-import") (part "C-EUC0603"))
    )
    (comp (ref "TP1")
      (value "TPB1,27")
      (footprint "eagle-import:B1,27")
      (libsource (lib "eagle-import") (part "TPB1,27"))
    )
    (comp (ref "U$4")
      (value "ASE")
      (footprint "eagle-import:ASE")
      (libsource (lib "eagle-import") (part "ASE"))
    )
    (comp (ref "U1")
      (value "MPU-6000QFN-24")
      (footprint "eagle-import:QFN-24-TESTING")
      (libsource (lib "eagle-import") (part "MPU-6000QFN-24"))
    )
    (comp (ref "U2")
      (value "MPU-6000QFN-24")
      (footprint "eagle-import:QFN-24-TESTING")
      (libsource (lib "eagle-import") (part "MPU-6000QFN-24"))
    )
  )
  (nets
    (net (code "1") (name "+3V3") (class "Default")
      (node (ref "C14") (pin "1") (pinfunction "1_1") (pintype "passive"))
      (node (ref "C18") (pin "+") (pinfunction "+_+") (pintype "passive"))
      (node (ref "C21") (pin "1") (pinfunction "1_1") (pintype "passive"))
      (node (ref "C26") (pin "1") (pinfunction "1_1") (pintype "passive"))
      (node (ref "C46") (pin "1") (pinfunction "1_1") (pintype "passive"))
      (node (ref "C47") (pin "1") (pinfunction "1_1") (pintype "passive"))
      (node (ref "C48") (pin "1") (pinfunction "1_1") (pintype "passive"))
      (node (ref "C49") (pin "1") (pinfunction "1_1") (pintype "passive"))
      (node (ref "C53") (pin "2") (pinfunction "2_2") (pintype "passive"))
      (node (ref "D7") (pin "1") (pinfunction "A_1") (pintype "passive"))
      (node (ref "JP2") (pin "8") (pinfunction "8_8") (pintype "passive"))
      (node (ref "L1") (pin "1") (pinfunction "2_1") (pintype "passive"))
      (node (ref "R22") (pin "1") (pinfunction "1_1") (pintype "passive"))
      (node (ref "R5") (pin "2") (pinfunction "2_2") (pintype "passive"))
      (node (ref "R6") (pin "2") (pinfunction "2_2") (pintype "passive"))
      (node (ref "R9") (pin "1") (pinfunction "1_1") (pintype "passive"))
      (node (ref "TP1") (pin "TP") (pinfunction "TP_TP") (pintype "input"))
      (node (ref "U$14") (pin "1") (pinfunction "VREFH_1") (pintype "bidirectional"))
      (node (ref "U$14") (pin "14") (pinfunction "VCC_14") (pintype "bidirectional"))
      (node (ref "U$14") (pin "35") (pinfunction "VCC_USB_35") (pintype "bidirectional"))
      (node (ref "U$14") (pin "60") (pinfunction "VCC_60") (pintype "bidirectional"))
      (node (ref "U$3") (pin "P$2") (pinfunction "VBAT_P$2") (pintype "bidirectional"))
      (node (ref "U$4") (pin "1") (pinfunction "TRI_1") (pintype "input"))
      (node (ref "U$4") (pin "4") (pinfunction "VDD_4") (pintype "power_in"))
      (node (ref "U$6") (pin "P$3") (pinfunction "VOUT_P$3") (pintype "bidirectional"))
      (node (ref "U$6") (pin "P$8") (pinfunction "L2_P$8") (pintype "bidirectional"))
      (node (ref "U1") (pin "13") (pinfunction "VDD_13") (pintype "bidirectional"))
      (node (ref "U2") (pin "13") (pinfunction "VDD_13") (pintype "bidirectional"))
    )
    (net (code "2") (name "+19V") (class "Default")
      (node (ref "D1") (pin "A") (pinfunction "A_A") (pintype "passive"))
      (node (ref "R23") (pin "2") (pinfunction "2_2") (pintype "passive"))
      (node (ref "X2") (pin "14") (pinfunction "KL_14") (pintype "passive"))
      (node (ref "X2") (pin "16") (pinfunction "KL_16") (pintype "passive"))
    )
    (net (code "3") (name "5V") (class "Default")
      (node (ref "C100") (pin "+") (pinfunction "+_+") (pintype "passive"))
      (node (ref "C29") (pin "1") (pinfunction "1_1") (pintype "passive"))
      (node (ref "C32") (pin "1") (pinfunction "1_1") (pintype "passive"))
      (node (ref "C35") (pin "1") (pinfunction "1_1") (pintype "passive"))
      (node (ref "C38") (pin "1") (pinfunction "1_1") (pintype "passive"))
      (node (ref "C54") (pin "2") (pinfunction "2_2") (pintype "passive"))
      (node (ref "C57") (pin "1") (pinfunction "1_1") (pintype "passive"))
      (node (ref "D2") (pin "C") (pinfunction "C_C") (pintype "passive"))
      (node (ref "L7") (pin "2") (pinfunction "2_2") (pintype "passive"))
      (node (ref "R38") (pin "1") (pinfunction "1_1") (pintype "passive"))
      (node (ref "U$16") (pin "P$2") (pinfunction "VDD_P$2") (pintype "bidirectional"))
      (node (ref "U$17") (pin "P$2") (pinfunction "VDD_P$2") (pintype "bidirectional"))
      (node (ref "U$18") (pin "P$2") (pinfunction "VDD_P$2") (pintype "bidirectional"))
      (node (ref "U$19") (pin "P$2") (pinfunction "VDD_P$2") (pintype "bidirectional"))
      (node (ref "U$6") (pin "P$6") (pinfunction "VIN_P$6") (pintype "bidirectional"))
    )
    (net (code "4") (name "AN0") (class "Default")
      (node (ref "AN0") (pin "TP") (pinfunction "TP_TP") (pintype "input"))
      (node (ref "C12") (pin "1") (pinfunction "1_1") (pintype "passive"))
      (node (ref "R18") (pin "1") (pinfunction "1_1") (pintype "passive"))
      (node (ref "R23") (pin "1") (pinfunction "1_1") (pintype "passive"))
      (node (ref "U$14") (pin "76") (pinfunction "PE2/D10[A10/D10]/RXD12/SMISO12/SSCL12/RXDX12/SSLB3/MOSIB/IRQ7-DS/AN0_76") (pintype "bidirectional"))
    )
    (net (code "5") (name "AN1") (class "Default")
      (node (ref "C22") (pin "1") (pinfunction "1_1") (pintype "passive"))
      (node (ref "R35") (pin "2") (pinfunction "2_2") (pintype "passive"))
      (node (ref "U$14") (pin "75") (pinfunction "PE3/D11[A11/D11]/~{CTS12}/~{RTS12}/~{SS12}/MISOB/AN1_75") (pintype "bidirectional"))
    )
    (net (code "6") (name "AN3") (class "Default")
      (node (ref "C40") (pin "1") (pinfunction "1_1") (pintype "passive"))
      (node (ref "R36") (pin "2") (pinfunction "2_2") (pintype "passive"))
      (node (ref "U$14") (pin "73") (pinfunction "PE5/D13[A13/D13]/RSPCKB/IRQ5/AN3_73") (pintype "bidirectional"))
    )
    (net (code "7") (name "AVCC0") (class "Default")
      (node (ref "C13") (pin "1") (pinfunction "1_1") (pintype "passive"))
      (node (ref "L1") (pin "2") (pinfunction "1_2") (pintype "passive"))
      (node (ref "U$14") (pin "96") (pinfunction "VREFH0_96") (pintype "bidirectional"))
      (node (ref "U$14") (pin "97") (pinfunction "AVCC0_97") (pintype "bidirectional"))
    )
    (net (code "8") (name "BAT0_EN") (class "Default")
      (node (ref "U$14") (pin "63") (pinfunction "PA7/A7/MISOA_63") (pintype "bidirectional"))
      (node (ref "X2") (pin "9") (pinfunction "KL_9") (pintype "passive"))
    )
    (net (code "9") (name "BAT1_EN") (class "Default")
      (node (ref "U$14") (pin "59") (pinfunction "PB1/A9/TXD6/SMOSI6/SSDA6/IRQ4-DS_59") (pintype "bidirectional"))
      (node (ref "X2") (pin "11") (pinfunction "KL_11") (pintype "passive"))
    )
    (net (code "10") (name "BAT2_EN") (class "Default")
      (node (ref "U$14") (pin "58") (pinfunction "PB2/A10/~{CTS6}/~{RTS6}/~{SS6}_58") (pintype "bidirectional"))
      (node (ref "X2") (pin "13") (pinfunction "KL_13") (pintype "passive"))
    )
    (net (code "11") (name "BAT3_EN") (class "Default")
      (node (ref "U$14") (pin "57") (pinfunction "PB3/A11/SCK6_57") (pintype "bidirectional"))
      (node (ref "X2") (pin "15") (pinfunction "KL_15") (pintype "passive"))
    )
    (net (code "12") (name "BUZZER") (class "Default")
      (node (ref "R19") (pin "2") (pinfunction "2_2") (pintype "passive"))
      (node (ref "U$14") (pin "100") (pinfunction "P05/IRQ13/DA1_100") (pintype "bidirectional"))
    )
    (net (code "13") (name "COMPUTER_PWR") (class "Default")
      (node (ref "U$14") (pin "78") (pinfunction "PE0/D8[A8/D8]/SCK12/SSLB1/ANEX0_78") (pintype "bidirectional"))
      (node (ref "X2") (pin "28") (pinfunction "KL_28") (pintype "passive"))
    )
    (net (code "14") (name "CPOUT1") (class "Default")
      (node (ref "C20") (pin "1") (pinfunction "1_1") (pintype "passive"))
      (node (ref "U1") (pin "20") (pinfunction "CPOUT_20") (pintype "bidirectional"))
    )
    (net (code "15") (name "CPOUT2") (class "Default")
      (node (ref "C25") (pin "1") (pinfunction "1_1") (pintype "passive"))
      (node (ref "U2") (pin "20") (pinfunction "CPOUT_20") (pintype "bidirectional"))
    )
    (net (code "16") (name "D+") (class "Default")
      (node (ref "R25") (pin "2") (pinfunction "2_2") (pintype "passive"))
      (node (ref "U$2") (pin "D+") (pinfunction "D+_D+") (pintype "bidirectional"))
    )
    (net (code "17") (name "D-") (class "Default")
      (node (ref "R24") (pin "2") (pinfunction "2_2") (pintype "passive"))
      (node (ref "U$2") (pin "D-") (pinfunction "D-_D-") (pintype "bidirectional"))
    )
    (net (code "18") (name "D0") (class "Default")
      (node (ref "U$14") (pin "86") (pinfunction "PD0/D0[A0/D0]/IRQ0/AN008_86") (pintype "bidirectional"))
      (node (ref "U$3") (pin "P$4") (pinfunction "DB0_P$4") (pintype "bidirectional"))
    )
    (net (code "19") (name "D1") (class "Default")
      (node (ref "U$14") (pin "85") (pinfunction "PD1/D1[A1/D1]/MTIOC4B/IRQ1/AN009_85") (pintype "bidirectional"))
      (node (ref "U$3") (pin "P$5") (pinfunction "DB1_P$5") (pintype "bidirectional"))
    )
    (net (code "20") (name "D2") (class "Default")
      (node (ref "U$14") (pin "84") (pinfunction "PD2/D2[A2/D2]/MTIOC4D/IRQ2/AN010_84") (pintype "bidirectional"))
      (node (ref "U$3") (pin "P$6") (pinfunction "DB2_P$6") (pintype "bidirectional"))
    )
    (net (code "21") (name "D3") (class "Default")
      (node (ref "U$14") (pin "83") (pinfunction "PD3/D3[A3/D3]/~{POE8}/IRQ3/AN011_83") (pintype "bidirectional"))
      (node (ref "U$3") (pin "P$7") (pinfunction "DB3_P$7") (pintype "bidirectional"))
    )
    (net (code "22") (name "D4") (class "Default")
      (node (ref "U$14") (pin "82") (pinfunction "PD4/D4[A4/D4]/~{POE3}/IRQ4/AN012_82") (pintype "bidirectional"))
      (node (ref "U$3") (pin "P$8") (pinfunction "DB4_P$8") (pintype "bidirectional"))
    )
    (net (code "23") (name "D5") (class "Default")
      (node (ref "U$14") (pin "81") (pinfunction "PD5/D5[A5/D5]/MTIC5W/IRQ5/AN013_81") (pintype "bidirectional"))
      (node (ref "U$3") (pin "P$9") (pinfunction "DB5_P$9") (pintype "bidirectional"))
    )
    (net (code "24") (name "D6") (class "Default")
      (node (ref "U$14") (pin "80") (pinfunction "PD6/D6[A6/D6]/MTIC5V/IRQ6/AN6_80") (pintype "bidirectional"))
      (node (ref "U$3") (pin "P$10") (pinfunction "DB6_P$10") (pintype "bidirectional"))
    )
    (net (code "25") (name "D7") (class "Default")
      (node (ref "U$14") (pin "79") (pinfunction "PD7/D7[A7/D7]/MTIC5U/IRQ7/AN7_79") (pintype "bidirectional"))
      (node (ref "U$3") (pin "P$11") (pinfunction "DB7_P$11") (pintype "bidirectional"))
    )
    (net (code "26") (name "EMLE") (class "Default")
      (node (ref "EMLE") (pin "TP") (pinfunction "TP_TP") (pintype "input"))
      (node (ref "JP2") (pin "4") (pinfunction "4_4") (pintype "passive"))
      (node (ref "R15") (pin "1") (pinfunction "1_1") (pintype "passive"))
      (node (ref "U$14") (pin "2") (pinfunction "EMLE_2") (pintype "bidirectional"))
    )
    (net (code "27") (name "ENABLE_PWR") (class "Default")
      (node (ref "U$14") (pin "34") (pinfunction "P12/RXD2/SMISO2/SSCL2/SCL0[FM+]/IRQ2_34") (pintype "bidirectional"))
      (node (ref "X2") (pin "30") (pinfunction "KL_30") (pintype "passive"))
    )
    (net (code "28") (name "EXTAL") (class "Default")
      (node (ref "C7") (pin "2") (pinfunction "2_2") (pintype "passive"))
      (node (ref "U$14") (pin "13") (pinfunction "EXTAL/P36_13") (pintype "bidirectional"))
      (node (ref "X1") (pin "P$2") (pinfunction "P$2_P$2") (pintype "bidirectional"))
    )
    (net (code "29") (name "GND") (class "Default")
      (node (ref "C1") (pin "2") (pinfunction "2_2") (pintype "passive"))
      (node (ref "C10") (pin "2") (pinfunction "2_2") (pintype "passive"))
      (node (ref "C100") (pin "-") (pinfunction "-_-") (pintype "passive"))
      (node (ref "C11") (pin "1") (pinfunction "1_1") (pintype "passive"))
      (node (ref "C12") (pin "2") (pinfunction "2_2") (pintype "passive"))
      (node (ref "C13") (pin "2") (pinfunction "2_2") (pintype "passive"))
      (node (ref "C14") (pin "2") (pinfunction "2_2") (pintype "passive"))
      (node (ref "C15") (pin "2") (pinfunction "2_2") (pintype "passive"))
      (node (ref "C17") (pin "2") (pinfunction "2_2") (pintype "passive"))
      (node (ref "C18") (pin "-") (pinfunction "-_-") (pintype "passive"))
      (node (ref "C19") (pin "2") (pinfunction "2_2") (pintype "passive"))
      (node (ref "C2") (pin "2") (pinfunction "2_2") (pintype "passive"))
      (node (ref "C20") (pin "2") (pinfunction "2_2") (pintype "passive"))
      (node (ref "C21") (pin "2") (pinfunction "2_2") (pintype "passive"))
      (node (ref "C22") (pin "2") (pinfunction "2_2") (pintype "passive"))
      (node (ref "C24") (pin "2") (pinfunction "2_2") (pintype "passive"))
      (node (ref "C25") (pin "2") (pinfunction "2_2") (pintype "passive"))
      (node (ref "C26") (pin "2") (pinfunction "2_2") (pintype "passive"))
      (node (ref "C29") (pin "2") (pinfunction "2_2") (pintype "passive"))
      (node (ref "C3") (pin "2") (pinfunction "2_2") (pintype "passive"))
      (node (ref "C30") (pin "2") (pinfunction "2_2") (pintype "passive"))
      (node (ref "C32") (pin "2") (pinfunction "2_2") (pintype "passive"))
      (node (ref "C33") (pin "2") (pinfunction "2_2") (pintype "passive"))
      (node (ref "C35") (pin "2") (pinfunction "2_2") (pintype "passive"))
      (node (ref "C36") (pin "2") (pinfunction "2_2") (pintype "passive"))
      (node (ref "C38") (pin "2") (pinfunction "2_2") (pintype "passive"))
      (node (ref "C39") (pin "2") (pinfunction "2_2") (pintype "passive"))
      (node (ref "C4") (pin "1") (pinfunction "1_1") (pintype "passive"))
      (node (ref "C40") (pin "2") (pinfunction "2_2") (pintype "passive"))
      (node (ref "C42") (pin "2") (pinfunction "2_2") (pintype "passive"))
      (node (ref "C43") (pin "2") (pinfunction "2_2") (pintype "passive"))
      (node (ref "C44") (pin "2") (pinfunction "2_2") (pintype "passive"))
      (node (ref "C45") (pin "2") (pinfunction "2_2") (pintype "passive"))
      (node (ref "C46") (pin "2") (pinfunction "2_2") (pintype "passive"))
      (node (ref "C47") (pin "2") (pinfunction "2_2") (pintype "passive"))
      (node (ref "C48") (pin "2") (pinfunction "2_2") (pintype "passive"))
      (node (ref "C49") (pin "2") (pinfunction "2_2") (pintype "passive"))
      (node (ref "C5") (pin "2") (pinfunction "2_2") (pintype "passive"))
      (node (ref "C50") (pin "2") (pinfunction "2_2") (pintype "passive"))
      (node (ref "C51") (pin "2") (pinfunction "2_2") (pintype "passive"))
      (node (ref "C53") (pin "1") (pinfunction "1_1") (pintype "passive"))
      (node (ref "C54") (pin "1") (pinfunction "1_1") (pintype "passive"))
      (node (ref "C55") (pin "1") (pinfunction "1_1") (pintype "passive"))
      (node (ref "C56") (pin "2") (pinfunction "2_2") (pintype "passive"))
      (node (ref "C57") (pin "2") (pinfunction "2_2") (pintype "passive"))
      (node (ref "C58") (pin "-") (pinfunction "-_-") (pintype "passive"))
      (node (ref "C6") (pin "1") (pinfunction "1_1") (pintype "passive"))
      (node (ref "C7") (pin "1") (pinfunction "1_1") (pintype "passive"))
      (node (ref "C8") (pin "2") (pinfunction "2_2") (pintype "passive"))
      (node (ref "C9") (pin "1") (pinfunction "1_1") (pintype "passive"))
      (node (ref "D100") (pin "1") (pinfunction "A_1") (pintype "passive"))
      (node (ref "D8") (pin "2") (pinfunction "CATHODE_2") (pintype "bidirectional"))
      (node (ref "JP2") (pin "12") (pinfunction "12_12") (pintype "passive"))
      (node (ref "JP2") (pin "14") (pinfunction "14_14") (pintype "passive"))
      (node (ref "JP2") (pin "2") (pinfunction "2_2") (pintype "passive"))
      (node (ref "R12") (pin "1") (pinfunction "1_1") (pintype "passive"))
      (node (ref "R13") (pin "2") (pinfunction "2_2") (pintype "passive"))
      (node (ref "R14") (pin "1") (pinfunction "1_1") (pintype "passive"))
      (node (ref "R15") (pin "2") (pinfunction "2_2") (pintype "passive"))
      (node (ref "R17") (pin "2") (pinfunction "2_2") (pintype "passive"))
      (node (ref "R18") (pin "2") (pinfunction "2_2") (pintype "passive"))
      (node (ref "R2") (pin "2") (pinfunction "2_2") (pintype "passive"))
      (node (ref "R21") (pin "1") (pinfunction "1_1") (pintype "passive"))
      (node (ref "R26") (pin "2") (pinfunction "2_2") (pintype "passive"))
      (node (ref "R28") (pin "1") (pinfunction "1_1") (pintype "passive"))
      (node (ref "R29") (pin "1") (pinfunction "1_1") (pintype "passive"))
      (node (ref "R30") (pin "1") (pinfunction "1_1") (pintype "passive"))
      (node (ref "R31") (pin "1") (pinfunction "1_1") (pintype "passive"))
      (node (ref "R37") (pin "2") (pinfunction "2_2") (pintype "passive"))
      (node (ref "R4") (pin "2") (pinfunction "2_2") (pintype "passive"))
      (node (ref "R45") (pin "1") (pinfunction "1_1") (pintype "passive"))
      (node (ref "R7") (pin "1") (pinfunction "1_1") (pintype "passive"))
      (node (ref "R8") (pin "1") (pinfunction "1_1") (pintype "passive"))
      (node (ref "S1") (pin "2") (pinfunction "2_2") (pintype "passive"))
      (node (ref "S2") (pin "1") (pinfunction "1_1") (pintype "passive"))
      (node (ref "S2") (pin "2") (pinfunction "2_2") (pintype "passive"))
      (node (ref "S6") (pin "1") (pinfunction "1_1") (pintype "passive"))
      (node (ref "S6") (pin "2") (pinfunction "2_2") (pintype "passive"))
      (node (ref "S7") (pin "1") (pinfunction "1_1") (pintype "passive"))
      (node (ref "S7") (pin "2") (pinfunction "2_2") (pintype "passive"))
      (node (ref "S8") (pin "1") (pinfunction "1_1") (pintype "passive"))
      (node (ref "S8") (pin "2") (pinfunction "2_2") (pintype "passive"))
      (node (ref "S9") (pin "2") (pinfunction "2_2") (pintype "passive"))
      (node (ref "SG1") (pin "2") (pinfunction "2_2") (pintype "passive"))
      (node (ref "U$1") (pin "N") (pinfunction "N_N") (pintype "bidirectional"))
      (node (ref "U$14") (pin "12") (pinfunction "VSS_12") (pintype "bidirectional"))
      (node (ref "U$14") (pin "3") (pinfunction "VREFL_3") (pintype "bidirectional"))
      (node (ref "U$14") (pin "38") (pinfunction "VSS_USB_38") (pintype "bidirectional"))
      (node (ref "U$14") (pin "62") (pinfunction "VSS_62") (pintype "bidirectional"))
      (node (ref "U$14") (pin "94") (pinfunction "VREFL0_94") (pintype "bidirectional"))
      (node (ref "U$14") (pin "99") (pinfunction "AVSS0_99") (pintype "bidirectional"))
      (node (ref "U$16") (pin "P$3") (pinfunction "GND_P$3") (pintype "bidirectional"))
      (node (ref "U$16") (pin "PAD@1") (pinfunction "PAD_PAD@1") (pintype "bidirectional"))
      (node (ref "U$17") (pin "P$3") (pinfunction "GND_P$3") (pintype "bidirectional"))
      (node (ref "U$17") (pin "PAD@1") (pinfunction "PAD_PAD@1") (pintype "bidirectional"))
      (node (ref "U$18") (pin "P$3") (pinfunction "GND_P$3") (pintype "bidirectional"))
      (node (ref "U$18") (pin "PAD@1") (pinfunction "PAD_PAD@1") (pintype "bidirectional"))
      (node (ref "U$19") (pin "P$3") (pinfunction "GND_P$3") (pintype "bidirectional"))
      (node (ref "U$19") (pin "PAD@1") (pinfunction "PAD_PAD@1") (pintype "bidirectional"))
      (node (ref "U$2") (pin "GND") (pinfunction "GND_GND") (pintype "bidirectional"))
      (node (ref "U$2") (pin "S1") (pinfunction "P$1_S1") (pintype "bidirectional"))
      (node (ref "U$2") (pin "S2") (pinfunction "P$2_S2") (pintype "bidirectional"))
      (node (ref "U$3") (pin "P$1") (pinfunction "VSS_P$1") (pintype "bidirectional"))
      (node (ref "U$4") (pin "2") (pinfunction "GND_2") (pintype "power_in"))
      (node (ref "U$5") (pin "7") (pinfunction "GND_7") (pintype "bidirectional"))
      (node (ref "U$6") (pin "P$2") (pinfunction "GND_P$2") (pintype "bidirectional"))
      (node (ref "U$6") (pin "P$5") (pinfunction "GND_P$5") (pintype "bidirectional"))
      (node (ref "U$6") (pin "PAD") (pinfunction "PAD_PAD") (pintype "bidirectional"))
      (node (ref "U1") (pin "18") (pinfunction "GND_18") (pintype "bidirectional"))
      (node (ref "U2") (pin "18") (pinfunction "GND_18") (pintype "bidirectional"))
      (node (ref "X2") (pin "10") (pinfunction "KL_10") (pintype "passive"))
      (node (ref "X2") (pin "17") (pinfunction "KL_17") (pintype "passive"))
      (node (ref "X3") (pin "2") (pinfunction "S_2") (pintype "passive"))
    )
    (net (code "30") (name "IBAT0_AD") (class "Default")
      (node (ref "C17") (pin "1") (pinfunction "1_1") (pintype "passive"))
      (node (ref "U$14") (pin "90") (pinfunction "P44/IRQ12-DS/AN004_90") (pintype "bidirectional"))
      (node (ref "X2") (pin "19") (pinfunction "KL_19") (pintype "passive"))
    )
    (net (code "31") (name "IBAT1_AD") (class "Default")
      (node (ref "C10") (pin "1") (pinfunction "1_1") (pintype "passive"))
      (node (ref "U$14") (pin "89") (pinfunction "P45/IRQ13-DS/AN005_89") (pintype "bidirectional"))
      (node (ref "X2") (pin "21") (pinfunction "KL_21") (pintype "passive"))
    )
    (net (code "32") (name "IBAT2_AD") (class "Default")
      (node (ref "C3") (pin "1") (pinfunction "1_1") (pintype "passive"))
      (node (ref "U$14") (pin "88") (pinfunction "P46/IRQ14-DS/AN006_88") (pintype "bidirectional"))
      (node (ref "X2") (pin "23") (pinfunction "KL_23") (pintype "passive"))
    )
    (net (code "33") (name "IBAT3_AD") (class "Default")
      (node (ref "C5") (pin "1") (pinfunction "1_1") (pintype "passive"))
      (node (ref "U$14") (pin "87") (pinfunction "P47/IRQ15-DS/AN007_87") (pintype "bidirectional"))
      (node (ref "X2") (pin "25") (pinfunction "KL_25") (pintype "passive"))
    )
    (net (code "34") (name "IMON1") (class "Default")
      (node (ref "R35") (pin "1") (pinfunction "1_1") (pintype "passive"))
      (node (ref "X2") (pin "27") (pinfunction "KL_27") (pintype "passive"))
    )
    (net (code "35") (name "IMON2") (class "Default")
      (node (ref "R36") (pin "1") (pinfunction "1_1") (pintype "passive"))
      (node (ref "X2") (pin "29") (pinfunction "KL_29") (pintype "passive"))
    )
    (net (code "36") (name "INT_GYRO1") (class "Default")
      (node (ref "U$14") (pin "51") (pinfunction "PC1/A17/SCK5/SSLA2/IRQ12_51") (pintype "bidirectional"))
      (node (ref "U1") (pin "12") (pinfunction "INT_12") (pintype "bidirectional"))
    )
    (net (code "37") (name "INT_GYRO2") (class "Default")
      (node (ref "U$14") (pin "52") (pinfunction "PC0/A16/~{CTS5}/~{RTS5}/~{SS5}/SSLA1/IRQ14_52") (pintype "bidirectional"))
      (node (ref "U2") (pin "12") (pinfunction "INT_12") (pintype "bidirectional"))
    )
    (net (code "38") (name "LED0") (class "Default")
      (node (ref "LED0") (pin "A") (pinfunction "A_A") (pintype "passive"))
      (node (ref "TPLED0") (pin "TP") (pinfunction "TP_TP") (pintype "input"))
      (node (ref "U$14") (pin "28") (pinfunction "P20/TXD0/SMOSI0/SSDA0/IRQ8_28") (pintype "bidirectional"))
    )
    (net (code "39") (name "LED1") (class "Default")
      (node (ref "LED1") (pin "A") (pinfunction "A_A") (pintype "passive"))
      (node (ref "TPLED1") (pin "TP") (pinfunction "TP_TP") (pintype "input"))
      (node (ref "U$14") (pin "27") (pinfunction "P21/RXD0/SMISO0/SSCL0/IRQ9_27") (pintype "bidirectional"))
    )
    (net (code "40") (name "LED2") (class "Default")
      (node (ref "LED2") (pin "A") (pinfunction "A_A") (pintype "passive"))
      (node (ref "TPLED2") (pin "TP") (pinfunction "TP_TP") (pintype "input"))
      (node (ref "U$14") (pin "26") (pinfunction "P22/SCK0_26") (pintype "bidirectional"))
    )
    (net (code "41") (name "LED3") (class "Default")
      (node (ref "LED3") (pin "A") (pinfunction "A_A") (pintype "passive"))
      (node (ref "TPLED3") (pin "TP") (pinfunction "TP_TP") (pintype "input"))
      (node (ref "U$14") (pin "25") (pinfunction "P23/TXD3/~{CTS0}/~{RTS0}/SMOSI3/~{SS0}/SSDA3_25") (pintype "bidirectional"))
    )
    (net (code "42") (name "LED4") (class "Default")
      (node (ref "LED4") (pin "A") (pinfunction "A_A") (pintype "passive"))
      (node (ref "TPLED4") (pin "TP") (pinfunction "TP_TP") (pintype "input"))
      (node (ref "U$14") (pin "24") (pinfunction "P24/~{CS4}/SCK3_24") (pintype "bidirectional"))
    )
    (net (code "43") (name "LED5") (class "Default")
      (node (ref "LED5") (pin "A") (pinfunction "A_A") (pintype "passive"))
      (node (ref "TPLED5") (pin "TP") (pinfunction "TP_TP") (pintype "input"))
      (node (ref "U$14") (pin "23") (pinfunction "P25/~{CS5}/RXD3/SMISO3/SSCL3/~{ADTRG0}_23") (pintype "bidirectional"))
    )
    (net (code "44") (name "LED6{slash}TDO") (class "Default")
      (node (ref "JP2") (pin "5") (pinfunction "5_5") (pintype "passive"))
      (node (ref "LED6") (pin "A") (pinfunction "A_A") (pintype "passive"))
      (node (ref "TPLED6") (pin "TP") (pinfunction "TP_TP") (pintype "input"))
      (node (ref "U$14") (pin "22") (pinfunction "TDO/P26/~{CS6}/TXD1/~{CTS3}/~{RTS3}/SMOSI1/~{SS3}/SSDA1/MOSIB_22") (pintype "bidirectional"))
    )
    (net (code "45") (name "LED7{slash}TCK") (class "Default")
      (node (ref "JP2") (pin "1") (pinfunction "1_1") (pintype "passive"))
      (node (ref "JP2") (pin "11") (pinfunction "11_11") (pintype "passive"))
      (node (ref "LED7") (pin "A") (pinfunction "A_A") (pintype "passive"))
      (node (ref "TPLED7") (pin "TP") (pinfunction "TP_TP") (pintype "input"))
      (node (ref "U$14") (pin "21") (pinfunction "TCK/FINEC/P27/~{CS7}/MTIOC2B/TMCI3/PO7/SCK1/RSPCKB_21") (pintype "bidirectional"))
    )
    (net (code "46") (name "LED_BLUE") (class "Default")
      (node (ref "R34") (pin "2") (pinfunction "2_2") (pintype "passive"))
      (node (ref "U$14") (pin "33") (pinfunction "P13/TXD2/SMOSI2/SSDA2/SDA0[FM+]/IRQ3/~{ADTRG}_33") (pintype "bidirectional"))
    )
    (net (code "47") (name "LED_GREEN") (class "Default")
      (node (ref "R33") (pin "2") (pinfunction "2_2") (pintype "passive"))
      (node (ref "U$14") (pin "31") (pinfunction "P15/RXD1/SCK3/SMISO1/SSCL1/CRX1-DS/IRQ5_31") (pintype "bidirectional"))
    )
    (net (code "48") (name "LED_RED") (class "Default")
      (node (ref "R32") (pin "2") (pinfunction "2_2") (pintype "passive"))
      (node (ref "U$14") (pin "29") (pinfunction "P17/SCK1/TXD3/SMOSI3/SSDA3/MISOA/SDA2-DS/IETXD/IRQ7/~{ADTRG}_29") (pintype "bidirectional"))
    )
    (net (code "49") (name "LX") (class "Default")
      (node (ref "U$6") (pin "P$1") (pinfunction "LX_P$1") (pintype "bidirectional"))
      (node (ref "U$6") (pin "P$7") (pinfunction "L1_P$7") (pintype "bidirectional"))
    )
    (net (code "50") (name "MD") (class "Default")
      (node (ref "JP2") (pin "7") (pinfunction "7_7") (pintype "passive"))
      (node (ref "R5") (pin "1") (pinfunction "1_1") (pintype "passive"))
      (node (ref "S1") (pin "1") (pinfunction "1_1") (pintype "passive"))
      (node (ref "U$14") (pin "7") (pinfunction "MD/FINED_7") (pintype "bidirectional"))
    )
    (net (code "51") (name "MISOA") (class "Default")
      (node (ref "R9") (pin "2") (pinfunction "2_2") (pintype "passive"))
      (node (ref "U$14") (pin "45") (pinfunction "PC7/A23/~{CS0}/TXD8/SMOSI8/SSDA8/MISOA/IRQ14_45") (pintype "bidirectional"))
      (node (ref "U2") (pin "9") (pinfunction "AD0/SDO_9") (pintype "bidirectional"))
    )
    (net (code "52") (name "MISOB") (class "Default")
      (node (ref "U$14") (pin "71") (pinfunction "PE7/D15[A15/D15]/MISOB/IRQ7/AN5_71") (pintype "bidirectional"))
      (node (ref "U1") (pin "9") (pinfunction "AD0/SDO_9") (pintype "bidirectional"))
    )
    (net (code "53") (name "MOSIA") (class "Default")
      (node (ref "U$14") (pin "46") (pinfunction "PC6/A22/~{CS1}/RXD8/SMISO8/SSCL8/MOSIA/IRQ13_46") (pintype "bidirectional"))
      (node (ref "U2") (pin "24") (pinfunction "SDA/SDI_24") (pintype "bidirectional"))
    )
    (net (code "54") (name "MOSIB") (class "Default")
      (node (ref "U$14") (pin "72") (pinfunction "PE6/D14[A14/D14]/MOSIB/IRQ6/AN4_72") (pintype "bidirectional"))
      (node (ref "U1") (pin "24") (pinfunction "SDA/SDI_24") (pintype "bidirectional"))
    )
    (net (code "55") (name "N$5") (class "Default")
      (node (ref "U1") (pin "1") (pinfunction "CLKIN_1") (pintype "bidirectional"))
    )
    (net (code "56") (name "N$7") (class "Default")
      (node (ref "U2") (pin "1") (pinfunction "CLKIN_1") (pintype "bidirectional"))
    )
    (net (code "57") (name "NMI") (class "Default")
      (node (ref "R6") (pin "1") (pinfunction "1_1") (pintype "passive"))
      (node (ref "U$14") (pin "15") (pinfunction "P35/NMI_15") (pintype "bidirectional"))
    )
    (net (code "58") (name "Net-(C52-Pad2)") (class "Default")
      (node (ref "C52") (pin "2") (pinfunction "2_2") (pintype "passive"))
      (node (ref "R21") (pin "2") (pinfunction "2_2") (pintype "passive"))
    )
    (net (code "59") (name "Net-(D8-BLUE_CATHODE)") (class "Default")
      (node (ref "D8") (pin "4") (pinfunction "BLUE_CATHODE_4") (pintype "bidirectional"))
      (node (ref "R34") (pin "1") (pinfunction "1_1") (pintype "passive"))
    )
    (net (code "60") (name "Net-(D8-GREEN_CATHODE)") (class "Default")
      (node (ref "D8") (pin "3") (pinfunction "GREEN_CATHODE_3") (pintype "bidirectional"))
      (node (ref "R33") (pin "1") (pinfunction "1_1") (pintype "passive"))
    )
    (net (code "61") (name "Net-(D8-RED_CATHODE)") (class "Default")
      (node (ref "D8") (pin "1") (pinfunction "RED_CATHODE_1") (pintype "bidirectional"))
      (node (ref "R32") (pin "1") (pinfunction "1_1") (pintype "passive"))
    )
    (net (code "62") (name "Net-(D100-C)") (class "Default")
      (node (ref "C28") (pin "1") (pinfunction "1_1") (pintype "passive"))
      (node (ref "D100") (pin "3") (pinfunction "C_3") (pintype "passive"))
      (node (ref "L7") (pin "1") (pinfunction "1_1") (pintype "passive"))
      (node (ref "U$5") (pin "8") (pinfunction "PH_8") (pintype "bidirectional"))
    )
    (net (code "63") (name "Net-(LED0-PadC)") (class "Default")
      (node (ref "LED0") (pin "C") (pinfunction "C_C") (pintype "passive"))
      (node (ref "R7") (pin "2") (pinfunction "2_2") (pintype "passive"))
    )
    (net (code "64") (name "Net-(LED1-PadC)") (class "Default")
      (node (ref "LED1") (pin "C") (pinfunction "C_C") (pintype "passive"))
      (node (ref "R8") (pin "2") (pinfunction "2_2") (pintype "passive"))
    )
    (net (code "65") (name "Net-(LED2-PadC)") (class "Default")
      (node (ref "LED2") (pin "C") (pinfunction "C_C") (pintype "passive"))
      (node (ref "R12") (pin "2") (pinfunction "2_2") (pintype "passive"))
    )
    (net (code "66") (name "Net-(LED3-PadC)") (class "Default")
      (node (ref "LED3") (pin "C") (pinfunction "C_C") (pintype "passive"))
      (node (ref "R14") (pin "2") (pinfunction "2_2") (pintype "passive"))
    )
    (net (code "67") (name "Net-(LED4-PadC)") (class "Default")
      (node (ref "LED4") (pin "C") (pinfunction "C_C") (pintype "passive"))
      (node (ref "R28") (pin "2") (pinfunction "2_2") (pintype "passive"))
    )
    (net (code "68") (name "Net-(LED5-PadC)") (class "Default")
      (node (ref "LED5") (pin "C") (pinfunction "C_C") (pintype "passive"))
      (node (ref "R29") (pin "2") (pinfunction "2_2") (pintype "passive"))
    )
    (net (code "69") (name "Net-(LED6-PadC)") (class "Default")
      (node (ref "LED6") (pin "C") (pinfunction "C_C") (pintype "passive"))
      (node (ref "R30") (pin "2") (pinfunction "2_2") (pintype "passive"))
    )
    (net (code "70") (name "Net-(LED7-PadC)") (class "Default")
      (node (ref "LED7") (pin "C") (pinfunction "C_C") (pintype "passive"))
      (node (ref "R31") (pin "2") (pinfunction "2_2") (pintype "passive"))
    )
    (net (code "71") (name "Net-(R19-Pad1)") (class "Default")
      (node (ref "R19") (pin "1") (pinfunction "1_1") (pintype "passive"))
      (node (ref "SG1") (pin "1") (pinfunction "1_1") (pintype "passive"))
    )
    (net (code "72") (name "Net-(U$4-OUT)") (class "Default")
      (node (ref "U$4") (pin "3") (pinfunction "OUT_3") (pintype "output"))
      (node (ref "U1") (pin "11") (pinfunction "FSYNC_11") (pintype "bidirectional"))
      (node (ref "U2") (pin "11") (pinfunction "FSYNC_11") (pintype "bidirectional"))
    )
    (net (code "73") (name "Net-(U$5-BOOT)") (class "Default")
      (node (ref "C28") (pin "2") (pinfunction "2_2") (pintype "passive"))
      (node (ref "U$5") (pin "1") (pinfunction "BOOT_1") (pintype "bidirectional"))
    )
    (net (code "74") (name "Net-(U$5-COMP)") (class "Default")
      (node (ref "C51") (pin "1") (pinfunction "1_1") (pintype "passive"))
      (node (ref "C52") (pin "1") (pinfunction "1_1") (pintype "passive"))
      (node (ref "U$5") (pin "6") (pinfunction "COMP_6") (pintype "bidirectional"))
    )
    (net (code "75") (name "Net-(U$5-EN)") (class "Default")
      (node (ref "R20") (pin "1") (pinfunction "1_1") (pintype "passive"))
      (node (ref "R45") (pin "2") (pinfunction "2_2") (pintype "passive"))
      (node (ref "U$5") (pin "3") (pinfunction "EN_3") (pintype "bidirectional"))
    )
    (net (code "76") (name "Net-(U$5-SS)") (class "Default")
      (node (ref "C55") (pin "2") (pinfunction "2_2") (pintype "passive"))
      (node (ref "U$5") (pin "4") (pinfunction "SS_4") (pintype "bidirectional"))
    )
    (net (code "77") (name "Net-(U$5-VSENSE)") (class "Default")
      (node (ref "R37") (pin "1") (pinfunction "1_1") (pintype "passive"))
      (node (ref "R38") (pin "2") (pinfunction "2_2") (pintype "passive"))
      (node (ref "U$5") (pin "5") (pinfunction "VSENSE_5") (pintype "bidirectional"))
    )
    (net (code "78") (name "Net-(U$14-P14{slash}~{CTS1}{slash}~{RTS1}{slash}~{SS1}{slash}CTX1{slash}USB0_DPUPE{slash}IRQ4)") (class "Default")
      (node (ref "R10") (pin "1") (pinfunction "1_1") (pintype "passive"))
      (node (ref "U$14") (pin "32") (pinfunction "P14/~{CTS1}/~{RTS1}/~{SS1}/CTX1/USB0_DPUPE/IRQ4_32") (pintype "bidirectional"))
    )
    (net (code "79") (name "Net-(U$14-VCL)") (class "Default")
      (node (ref "C4") (pin "2") (pinfunction "2_2") (pintype "passive"))
      (node (ref "U$14") (pin "5") (pinfunction "VCL_5") (pintype "bidirectional"))
    )
    (net (code "80") (name "Net-(U$16-BOOT)") (class "Default")
      (node (ref "C27") (pin "1") (pinfunction "1_1") (pintype "passive"))
      (node (ref "U$16") (pin "P$7") (pinfunction "BOOT_P$7") (pintype "bidirectional"))
    )
    (net (code "81") (name "Net-(U$16-BOOT_R)") (class "Default")
      (node (ref "C27") (pin "2") (pinfunction "2_2") (pintype "passive"))
      (node (ref "U$16") (pin "P$6") (pinfunction "BOOT_R_P$6") (pintype "bidirectional"))
    )
    (net (code "82") (name "Net-(U$17-BOOT)") (class "Default")
      (node (ref "C31") (pin "1") (pinfunction "1_1") (pintype "passive"))
      (node (ref "U$17") (pin "P$7") (pinfunction "BOOT_P$7") (pintype "bidirectional"))
    )
    (net (code "83") (name "Net-(U$17-BOOT_R)") (class "Default")
      (node (ref "C31") (pin "2") (pinfunction "2_2") (pintype "passive"))
      (node (ref "U$17") (pin "P$6") (pinfunction "BOOT_R_P$6") (pintype "bidirectional"))
    )
    (net (code "84") (name "Net-(U$18-BOOT)") (class "Default")
      (node (ref "C34") (pin "1") (pinfunction "1_1") (pintype "passive"))
      (node (ref "U$18") (pin "P$7") (pinfunction "BOOT_P$7") (pintype "bidirectional"))
    )
    (net (code "85") (name "Net-(U$18-BOOT_R)") (class "Default")
      (node (ref "C34") (pin "2") (pinfunction "2_2") (pintype "passive"))
      (node (ref "U$18") (pin "P$6") (pinfunction "BOOT_R_P$6") (pintype "bidirectional"))
    )
    (net (code "86") (name "Net-(U$19-BOOT)") (class "Default")
      (node (ref "C37") (pin "1") (pinfunction "1_1") (pintype "passive"))
      (node (ref "U$19") (pin "P$7") (pinfunction "BOOT_P$7") (pintype "bidirectional"))
    )
    (net (code "87") (name "Net-(U$19-BOOT_R)") (class "Default")
      (node (ref "C37") (pin "2") (pinfunction "2_2") (pintype "passive"))
      (node (ref "U$19") (pin "P$6") (pinfunction "BOOT_R_P$6") (pintype "bidirectional"))
    )
    (net (code "88") (name "OUT1_EN") (class "Default")
      (node (ref "U$14") (pin "55") (pinfunction "PB5/A13/SCK9_55") (pintype "bidirectional"))
      (node (ref "X2") (pin "18") (pinfunction "KL_18") (pintype "passive"))
    )
    (net (code "89") (name "OUT2_EN") (class "Default")
      (node (ref "U$14") (pin "53") (pinfunction "PB7/A15/TXD9/SMOSI9/SSDA9_53") (pintype "bidirectional"))
      (node (ref "X2") (pin "20") (pinfunction "KL_20") (pintype "passive"))
    )
    (net (code "90") (name "OUT3_EN") (class "Default")
      (node (ref "U$14") (pin "4") (pinfunction "PJ3/MTIOC3C/~{CTS6}/~{RTS6}/~{CTS0}/~{RTS0}/~{SS6}/~{SS0}_4") (pintype "bidirectional"))
      (node (ref "X2") (pin "22") (pinfunction "KL_22") (pintype "passive"))
    )
    (net (code "91") (name "OUT4_EN") (class "Default")
      (node (ref "U$14") (pin "41") (pinfunction "BCLK/P53_41") (pintype "bidirectional"))
      (node (ref "X2") (pin "24") (pinfunction "KL_24") (pintype "passive"))
    )
    (net (code "92") (name "OUT5_EN") (class "Default")
      (node (ref "U$14") (pin "98") (pinfunction "P07/IRQ15/~{ADTRG0}_98") (pintype "bidirectional"))
      (node (ref "X2") (pin "26") (pinfunction "KL_26") (pintype "passive"))
    )
    (net (code "93") (name "PGOOD1") (class "Default")
      (node (ref "U$14") (pin "49") (pinfunction "A19/TXD5/SMOSI5/SSDA5/IETXD_49") (pintype "bidirectional"))
      (node (ref "X2") (pin "31") (pinfunction "KL_31") (pintype "passive"))
    )
    (net (code "94") (name "PGOOD2") (class "Default")
      (node (ref "U$14") (pin "50") (pinfunction "PC2/A18/RXD5/SMISO5/SSCL5/SSLA3/IERXD_50") (pintype "bidirectional"))
      (node (ref "X2") (pin "33") (pinfunction "KL_33") (pintype "passive"))
    )
    (net (code "95") (name "PWM0") (class "Default")
      (node (ref "U$14") (pin "70") (pinfunction "PA0/A0/~{BC0}/SSLA1_70") (pintype "bidirectional"))
      (node (ref "U$16") (pin "P$8") (pinfunction "PWM_P$8") (pintype "bidirectional"))
    )
    (net (code "96") (name "PWM1") (class "Default")
      (node (ref "U$14") (pin "66") (pinfunction "PA4/A4/TXD5/SMOSI5/SSDA5/SSLA0/IRQ5-DS_66") (pintype "bidirectional"))
      (node (ref "U$17") (pin "P$8") (pinfunction "PWM_P$8") (pintype "bidirectional"))
    )
    (net (code "97") (name "PWM2") (class "Default")
      (node (ref "U$14") (pin "64") (pinfunction "PA6/A6/~{CTS5}/~{RTS5}/~{SS5}/MOSIA_64") (pintype "bidirectional"))
      (node (ref "U$18") (pin "P$8") (pinfunction "PWM_P$8") (pintype "bidirectional"))
    )
    (net (code "98") (name "PWM3") (class "Default")
      (node (ref "U$14") (pin "61") (pinfunction "PB0/A8/RXD6/SMISO6/SSCL6/RSPCKA/IRQ12_61") (pintype "bidirectional"))
      (node (ref "U$19") (pin "P$8") (pinfunction "PWM_P$8") (pintype "bidirectional"))
    )
    (net (code "99") (name "PWM4") (class "Default")
      (node (ref "U$14") (pin "56") (pinfunction "PB4/A12/~{CTS9}/~{RTS9}/~{SS9}_56") (pintype "bidirectional"))
      (node (ref "X2") (pin "34") (pinfunction "KL_34") (pintype "passive"))
    )
    (net (code "100") (name "PWM5") (class "Default")
      (node (ref "U$14") (pin "54") (pinfunction "PB6/A14/RXD9/SMISO9/SSCL9_54") (pintype "bidirectional"))
      (node (ref "X2") (pin "32") (pinfunction "KL_32") (pintype "passive"))
    )
    (net (code "101") (name "REGOUT1") (class "Default")
      (node (ref "C19") (pin "1") (pinfunction "1_1") (pintype "passive"))
      (node (ref "U1") (pin "10") (pinfunction "REGOUT_10") (pintype "bidirectional"))
    )
    (net (code "102") (name "REGOUT2") (class "Default")
      (node (ref "C24") (pin "1") (pinfunction "1_1") (pintype "passive"))
      (node (ref "U2") (pin "10") (pinfunction "REGOUT_10") (pintype "bidirectional"))
    )
    (net (code "103") (name "RSPCKA") (class "Default")
      (node (ref "U$14") (pin "47") (pinfunction "PC5/A21/~{CS2}/~{WAIT}/SCK8/RSPCKA_47") (pintype "bidirectional"))
      (node (ref "U2") (pin "23") (pinfunction "SCL/SCLK_23") (pintype "bidirectional"))
    )
    (net (code "104") (name "RSPCKB") (class "Default")
      (node (ref "U$14") (pin "77") (pinfunction "PE1/D9[A9/D9]/TXD12/SMOSI12/SSDA12/TXDX12/SIOX12/SSLB2/RSPCKB/ANEX1_77") (pintype "bidirectional"))
      (node (ref "U1") (pin "23") (pinfunction "SCL/SCLK_23") (pintype "bidirectional"))
    )
    (net (code "105") (name "SSLA0") (class "Default")
      (node (ref "U$14") (pin "48") (pinfunction "PC4/A20/~{CS3}/SCK5/~{CTS8}/~{RTS8}/~{SS8}/SSLA0_48") (pintype "bidirectional"))
      (node (ref "U2") (pin "8") (pinfunction "CS_8") (pintype "bidirectional"))
    )
    (net (code "106") (name "SSLB0") (class "Default")
      (node (ref "U$14") (pin "74") (pinfunction "PE4/D12[A12/D12]/SSLB0/AN2_74") (pintype "bidirectional"))
      (node (ref "U1") (pin "8") (pinfunction "CS_8") (pintype "bidirectional"))
    )
    (net (code "107") (name "SUPERCAP") (class "Default")
      (node (ref "D7") (pin "3") (pinfunction "C_3") (pintype "passive"))
      (node (ref "U$1") (pin "P") (pinfunction "P_P") (pintype "bidirectional"))
      (node (ref "U$14") (pin "6") (pinfunction "VBATT_6") (pintype "bidirectional"))
    )
    (net (code "108") (name "USB0_DM") (class "Default")
      (node (ref "R24") (pin "1") (pinfunction "1_1") (pintype "passive"))
      (node (ref "U$14") (pin "36") (pinfunction "USB0_DM_36") (pintype "bidirectional"))
    )
    (net (code "109") (name "USB0_DP") (class "Default")
      (node (ref "R10") (pin "2") (pinfunction "2_2") (pintype "passive"))
      (node (ref "R25") (pin "1") (pinfunction "1_1") (pintype "passive"))
      (node (ref "U$14") (pin "37") (pinfunction "USB0_DP_37") (pintype "bidirectional"))
    )
    (net (code "110") (name "USB0_VBUS") (class "Default")
      (node (ref "R26") (pin "1") (pinfunction "1_1") (pintype "passive"))
      (node (ref "R27") (pin "2") (pinfunction "2_2") (pintype "passive"))
      (node (ref "U$14") (pin "30") (pinfunction "P16/TXD1/RXD3/SMOSI1/SMISO3/SSDA1/SSCL3/MOSIA/SCL2-DS/IERXD/USB0_VBUS/IRQ6/~{ADTRG0}_30") (pintype "bidirectional"))
    )
    (net (code "111") (name "V+") (class "Default")
      (node (ref "C56") (pin "1") (pinfunction "1_1") (pintype "passive"))
      (node (ref "C58") (pin "+") (pinfunction "+_+") (pintype "passive"))
      (node (ref "R20") (pin "2") (pinfunction "2_2") (pintype "passive"))
      (node (ref "U$5") (pin "2") (pinfunction "VIN_2") (pintype "bidirectional"))
      (node (ref "X2") (pin "12") (pinfunction "KL_12") (pintype "passive"))
    )
    (net (code "112") (name "VBAT0") (class "Default")
      (node (ref "C42") (pin "1") (pinfunction "1_1") (pintype "passive"))
      (node (ref "L2") (pin "2") (pinfunction "2_2") (pintype "passive"))
      (node (ref "R16") (pin "1") (pinfunction "1_1") (pintype "passive"))
      (node (ref "X2") (pin "1") (pinfunction "KL_1") (pintype "passive"))
      (node (ref "X2") (pin "2") (pinfunction "KL_2") (pintype "passive"))
    )
    (net (code "113") (name "VBAT0_AD") (class "Default")
      (node (ref "C15") (pin "1") (pinfunction "1_1") (pintype "passive"))
      (node (ref "R16") (pin "2") (pinfunction "2_2") (pintype "passive"))
      (node (ref "R17") (pin "1") (pinfunction "1_1") (pintype "passive"))
      (node (ref "U$14") (pin "95") (pinfunction "P40/IRQ8-DS/AN000_95") (pintype "bidirectional"))
    )
    (net (code "114") (name "VBAT1") (class "Default")
      (node (ref "C43") (pin "1") (pinfunction "1_1") (pintype "passive"))
      (node (ref "L3") (pin "2") (pinfunction "2_2") (pintype "passive"))
      (node (ref "R11") (pin "1") (pinfunction "1_1") (pintype "passive"))
      (node (ref "X2") (pin "3") (pinfunction "KL_3") (pintype "passive"))
      (node (ref "X2") (pin "4") (pinfunction "KL_4") (pintype "passive"))
    )
    (net (code "115") (name "VBAT1_AD") (class "Default")
      (node (ref "C8") (pin "1") (pinfunction "1_1") (pintype "passive"))
      (node (ref "R11") (pin "2") (pinfunction "2_2") (pintype "passive"))
      (node (ref "R13") (pin "1") (pinfunction "1_1") (pintype "passive"))
      (node (ref "U$14") (pin "93") (pinfunction "P41/IRQ9-DS/AN001_93") (pintype "bidirectional"))
    )
    (net (code "116") (name "VBAT2") (class "Default")
      (node (ref "C44") (pin "1") (pinfunction "1_1") (pintype "passive"))
      (node (ref "L4") (pin "2") (pinfunction "2_2") (pintype "passive"))
      (node (ref "R3") (pin "1") (pinfunction "1_1") (pintype "passive"))
      (node (ref "X2") (pin "5") (pinfunction "KL_5") (pintype "passive"))
      (node (ref "X2") (pin "6") (pinfunction "KL_6") (pintype "passive"))
    )
    (net (code "117") (name "VBAT2_AD") (class "Default")
      (node (ref "C2") (pin "1") (pinfunction "1_1") (pintype "passive"))
      (node (ref "R3") (pin "2") (pinfunction "2_2") (pintype "passive"))
      (node (ref "R4") (pin "1") (pinfunction "1_1") (pintype "passive"))
      (node (ref "U$14") (pin "92") (pinfunction "P42/IRQ10-DS/AN002_92") (pintype "bidirectional"))
    )
    (net (code "118") (name "VBAT3") (class "Default")
      (node (ref "C45") (pin "1") (pinfunction "1_1") (pintype "passive"))
      (node (ref "L5") (pin "2") (pinfunction "2_2") (pintype "passive"))
      (node (ref "R1") (pin "1") (pinfunction "1_1") (pintype "passive"))
      (node (ref "X2") (pin "7") (pinfunction "KL_7") (pintype "passive"))
      (node (ref "X2") (pin "8") (pinfunction "KL_8") (pintype "passive"))
    )
    (net (code "119") (name "VBAT3_AD") (class "Default")
      (node (ref "C1") (pin "1") (pinfunction "1_1") (pintype "passive"))
      (node (ref "R1") (pin "2") (pinfunction "2_2") (pintype "passive"))
      (node (ref "R2") (pin "1") (pinfunction "1_1") (pintype "passive"))
      (node (ref "U$14") (pin "91") (pinfunction "P43/IRQ11-DS/AN003_91") (pintype "bidirectional"))
    )
    (net (code "120") (name "VBUS") (class "Default")
      (node (ref "D2") (pin "A") (pinfunction "A_A") (pintype "passive"))
      (node (ref "R27") (pin "1") (pinfunction "1_1") (pintype "passive"))
      (node (ref "U$2") (pin "VBUS") (pinfunction "VBUS_VBUS") (pintype "bidirectional"))
    )
    (net (code "121") (name "VIN") (class "Default")
      (node (ref "C30") (pin "1") (pinfunction "1_1") (pintype "passive"))
      (node (ref "C33") (pin "1") (pinfunction "1_1") (pintype "passive"))
      (node (ref "C36") (pin "1") (pinfunction "1_1") (pintype "passive"))
      (node (ref "C39") (pin "1") (pinfunction "1_1") (pintype "passive"))
      (node (ref "C50") (pin "1") (pinfunction "1_1") (pintype "passive"))
      (node (ref "D1") (pin "C") (pinfunction "C_C") (pintype "passive"))
      (node (ref "U$16") (pin "P$5A") (pinfunction "VIN_P$5A") (pintype "bidirectional"))
      (node (ref "U$16") (pin "P$5B") (pinfunction "VIN1_P$5B") (pintype "bidirectional"))
      (node (ref "U$16") (pin "P$5C") (pinfunction "VIN2_P$5C") (pintype "bidirectional"))
      (node (ref "U$16") (pin "P$5D") (pinfunction "VIN3_P$5D") (pintype "bidirectional"))
      (node (ref "U$16") (pin "P$5E") (pinfunction "VIN4_P$5E") (pintype "bidirectional"))
      (node (ref "U$16") (pin "P$5F") (pinfunction "VIN5_P$5F") (pintype "bidirectional"))
      (node (ref "U$17") (pin "P$5A") (pinfunction "VIN_P$5A") (pintype "bidirectional"))
      (node (ref "U$17") (pin "P$5B") (pinfunction "VIN1_P$5B") (pintype "bidirectional"))
      (node (ref "U$17") (pin "P$5C") (pinfunction "VIN2_P$5C") (pintype "bidirectional"))
      (node (ref "U$17") (pin "P$5D") (pinfunction "VIN3_P$5D") (pintype "bidirectional"))
      (node (ref "U$17") (pin "P$5E") (pinfunction "VIN4_P$5E") (pintype "bidirectional"))
      (node (ref "U$17") (pin "P$5F") (pinfunction "VIN5_P$5F") (pintype "bidirectional"))
      (node (ref "U$18") (pin "P$5A") (pinfunction "VIN_P$5A") (pintype "bidirectional"))
      (node (ref "U$18") (pin "P$5B") (pinfunction "VIN1_P$5B") (pintype "bidirectional"))
      (node (ref "U$18") (pin "P$5C") (pinfunction "VIN2_P$5C") (pintype "bidirectional"))
      (node (ref "U$18") (pin "P$5D") (pinfunction "VIN3_P$5D") (pintype "bidirectional"))
      (node (ref "U$18") (pin "P$5E") (pinfunction "VIN4_P$5E") (pintype "bidirectional"))
      (node (ref "U$18") (pin "P$5F") (pinfunction "VIN5_P$5F") (pintype "bidirectional"))
      (node (ref "U$19") (pin "P$5A") (pinfunction "VIN_P$5A") (pintype "bidirectional"))
      (node (ref "U$19") (pin "P$5B") (pinfunction "VIN1_P$5B") (pintype "bidirectional"))
      (node (ref "U$19") (pin "P$5C") (pinfunction "VIN2_P$5C") (pintype "bidirectional"))
      (node (ref "U$19") (pin "P$5D") (pinfunction "VIN3_P$5D") (pintype "bidirectional"))
      (node (ref "U$19") (pin "P$5E") (pinfunction "VIN4_P$5E") (pintype "bidirectional"))
      (node (ref "U$19") (pin "P$5F") (pinfunction "VIN5_P$5F") (pintype "bidirectional"))
    )
    (net (code "122") (name "VSW0") (class "Default")
      (node (ref "L2") (pin "1") (pinfunction "1_1") (pintype "passive"))
      (node (ref "U$16") (pin "P$4A") (pinfunction "VSW_P$4A") (pintype "bidirectional"))
      (node (ref "U$16") (pin "P$4B") (pinfunction "VSW1_P$4B") (pintype "bidirectional"))
      (node (ref "U$16") (pin "P$4C") (pinfunction "VSW2_P$4C") (pintype "bidirectional"))
      (node (ref "U$16") (pin "P$4D") (pinfunction "VSW3_P$4D") (pintype "bidirectional"))
      (node (ref "U$16") (pin "P$4E") (pinfunction "VSW4_P$4E") (pintype "bidirectional"))
      (node (ref "U$16") (pin "P$4F") (pinfunction "VSW5_P$4F") (pintype "bidirectional"))
    )
    (net (code "123") (name "VSW1") (class "Default")
      (node (ref "L3") (pin "1") (pinfunction "1_1") (pintype "passive"))
      (node (ref "U$17") (pin "P$4A") (pinfunction "VSW_P$4A") (pintype "bidirectional"))
      (node (ref "U$17") (pin "P$4B") (pinfunction "VSW1_P$4B") (pintype "bidirectional"))
      (node (ref "U$17") (pin "P$4C") (pinfunction "VSW2_P$4C") (pintype "bidirectional"))
      (node (ref "U$17") (pin "P$4D") (pinfunction "VSW3_P$4D") (pintype "bidirectional"))
      (node (ref "U$17") (pin "P$4E") (pinfunction "VSW4_P$4E") (pintype "bidirectional"))
      (node (ref "U$17") (pin "P$4F") (pinfunction "VSW5_P$4F") (pintype "bidirectional"))
    )
    (net (code "124") (name "VSW2") (class "Default")
      (node (ref "L4") (pin "1") (pinfunction "1_1") (pintype "passive"))
      (node (ref "U$18") (pin "P$4A") (pinfunction "VSW_P$4A") (pintype "bidirectional"))
      (node (ref "U$18") (pin "P$4B") (pinfunction "VSW1_P$4B") (pintype "bidirectional"))
      (node (ref "U$18") (pin "P$4C") (pinfunction "VSW2_P$4C") (pintype "bidirectional"))
      (node (ref "U$18") (pin "P$4D") (pinfunction "VSW3_P$4D") (pintype "bidirectional"))
      (node (ref "U$18") (pin "P$4E") (pinfunction "VSW4_P$4E") (pintype "bidirectional"))
      (node (ref "U$18") (pin "P$4F") (pinfunction "VSW5_P$4F") (pintype "bidirectional"))
    )
    (net (code "125") (name "VSW3") (class "Default")
      (node (ref "L5") (pin "1") (pinfunction "1_1") (pintype "passive"))
      (node (ref "U$19") (pin "P$4A") (pinfunction "VSW_P$4A") (pintype "bidirectional"))
      (node (ref "U$19") (pin "P$4B") (pinfunction "VSW1_P$4B") (pintype "bidirectional"))
      (node (ref "U$19") (pin "P$4C") (pinfunction "VSW2_P$4C") (pintype "bidirectional"))
      (node (ref "U$19") (pin "P$4D") (pinfunction "VSW3_P$4D") (pintype "bidirectional"))
      (node (ref "U$19") (pin "P$4E") (pinfunction "VSW4_P$4E") (pintype "bidirectional"))
      (node (ref "U$19") (pin "P$4F") (pinfunction "VSW5_P$4F") (pintype "bidirectional"))
    )
    (net (code "126") (name "XCIN") (class "Default")
      (node (ref "C9") (pin "2") (pinfunction "2_2") (pintype "passive"))
      (node (ref "Q1") (pin "1") (pinfunction "1_1") (pintype "passive"))
      (node (ref "U$14") (pin "8") (pinfunction "XCIN_8") (pintype "bidirectional"))
    )
    (net (code "127") (name "XCOUT") (class "Default")
      (node (ref "C11") (pin "2") (pinfunction "2_2") (pintype "passive"))
      (node (ref "Q1") (pin "4") (pinfunction "2_4") (pintype "passive"))
      (node (ref "U$14") (pin "9") (pinfunction "XCOUT_9") (pintype "bidirectional"))
    )
    (net (code "128") (name "XTAL") (class "Default")
      (node (ref "C6") (pin "2") (pinfunction "2_2") (pintype "passive"))
      (node (ref "U$14") (pin "11") (pinfunction "XTAL/P37_11") (pintype "bidirectional"))
      (node (ref "X1") (pin "P$1") (pinfunction "P$1_P$1") (pintype "bidirectional"))
    )
    (net (code "129") (name "unconnected-(JP2-Pad6)") (class "Default")
      (node (ref "JP2") (pin "6") (pinfunction "6_6") (pintype "passive"))
    )
    (net (code "130") (name "unconnected-(U$3-NC-PadP$3)") (class "Default")
      (node (ref "U$3") (pin "P$3") (pinfunction "NC_P$3") (pintype "bidirectional"))
    )
    (net (code "131") (name "unconnected-(U$6-CE-PadP$4)") (class "Default")
      (node (ref "U$6") (pin "P$4") (pinfunction "CE_P$4") (pintype "bidirectional"))
    )
    (net (code "132") (name "unconnected-(U1-AUXCL-Pad7)") (class "Default")
      (node (ref "U1") (pin "7") (pinfunction "AUXCL_7") (pintype "bidirectional"))
    )
    (net (code "133") (name "unconnected-(U1-AUXDA-Pad6)") (class "Default")
      (node (ref "U1") (pin "6") (pinfunction "AUXDA_6") (pintype "bidirectional"))
    )
    (net (code "134") (name "unconnected-(U1-CLKOUT-Pad22)") (class "Default")
      (node (ref "U1") (pin "22") (pinfunction "CLKOUT_22") (pintype "bidirectional"))
    )
    (net (code "135") (name "unconnected-(U2-AUXCL-Pad7)") (class "Default")
      (node (ref "U2") (pin "7") (pinfunction "AUXCL_7") (pintype "bidirectional"))
    )
    (net (code "136") (name "unconnected-(U2-AUXDA-Pad6)") (class "Default")
      (node (ref "U2") (pin "6") (pinfunction "AUXDA_6") (pintype "bidirectional"))
    )
    (net (code "137") (name "unconnected-(U2-CLKOUT-Pad22)") (class "Default")
      (node (ref "U2") (pin "22") (pinfunction "CLKOUT_22") (pintype "bidirectional"))
    )
    (net (code "138") (name "~{OLED_CS}") (class "Default")
      (node (ref "JP2") (pin "10") (pinfunction "10_10") (pintype "passive"))
      (node (ref "U$14") (pin "39") (pinfunction "P55/~{WAIT}/CRX1/IRQ10_39") (pintype "bidirectional"))
      (node (ref "U$3") (pin "P$16") (pinfunction "~{CS}_P$16") (pintype "bidirectional"))
    )
    (net (code "139") (name "~{OLED_DC}") (class "Default")
      (node (ref "U$14") (pin "40") (pinfunction "P54/ALE/~{CTS2}/~{RTS2}/~{SS2}/CTX1_40") (pintype "bidirectional"))
      (node (ref "U$3") (pin "P$14") (pinfunction "~{DC}_P$14") (pintype "bidirectional"))
    )
    (net (code "140") (name "~{OLED_RD}") (class "Default")
      (node (ref "U$14") (pin "42") (pinfunction "P52/~{RD}/RXD2/SMISO2/SSCL2/SSLB3_42") (pintype "bidirectional"))
      (node (ref "U$3") (pin "P$12") (pinfunction "~{RD}_P$12") (pintype "bidirectional"))
    )
    (net (code "141") (name "~{OLED_RESET}") (class "Default")
      (node (ref "U$14") (pin "43") (pinfunction "P51/~{WR1}/~{BC1}/~{WAIT}/SCK2/SSLB2_43") (pintype "bidirectional"))
      (node (ref "U$3") (pin "P$15") (pinfunction "~{RESET}_P$15") (pintype "bidirectional"))
    )
    (net (code "142") (name "~{OLED_WR}") (class "Default")
      (node (ref "U$14") (pin "44") (pinfunction "P50/~{WR0}/~{WR}/TXD2/SMOSI2/SSDA2/SSLB1_44") (pintype "bidirectional"))
      (node (ref "U$3") (pin "P$13") (pinfunction "~{WR}_P$13") (pintype "bidirectional"))
    )
    (net (code "143") (name "~{RESET}") (class "Default")
      (node (ref "JP2") (pin "13") (pinfunction "13_13") (pintype "passive"))
      (node (ref "R22") (pin "2") (pinfunction "2_2") (pintype "passive"))
      (node (ref "S9") (pin "1") (pinfunction "1_1") (pintype "passive"))
      (node (ref "U$14") (pin "10") (pinfunction "~{RES}_10") (pintype "bidirectional"))
    )
    (net (code "144") (name "~{SKIP0}") (class "Default")
      (node (ref "U$14") (pin "69") (pinfunction "PA1/A1/SCK5/SSLA2/IRQ11_69") (pintype "bidirectional"))
      (node (ref "U$16") (pin "P$1") (pinfunction "~{SKIP}_P$1") (pintype "bidirectional"))
    )
    (net (code "145") (name "~{SKIP1}") (class "Default")
      (node (ref "U$14") (pin "68") (pinfunction "PA2/A2/PO18/RXD5/SMISO5/SSCL5/SSLA3_68") (pintype "bidirectional"))
      (node (ref "U$17") (pin "P$1") (pinfunction "~{SKIP}_P$1") (pintype "bidirectional"))
    )
    (net (code "146") (name "~{SKIP2}") (class "Default")
      (node (ref "U$14") (pin "67") (pinfunction "PA3/A3/RXD5/SMISO5/SSCL5/IRQ6-DS_67") (pintype "bidirectional"))
      (node (ref "U$18") (pin "P$1") (pinfunction "~{SKIP}_P$1") (pintype "bidirectional"))
    )
    (net (code "147") (name "~{SKIP3}") (class "Default")
      (node (ref "U$14") (pin "65") (pinfunction "PA5/A5/RSPCKA_65") (pintype "bidirectional"))
      (node (ref "U$19") (pin "P$1") (pinfunction "~{SKIP}_P$1") (pintype "bidirectional"))
    )
    (net (code "148") (name "~{SW1}") (class "Default")
      (node (ref "S6") (pin "3") (pinfunction "3_3") (pintype "passive"))
      (node (ref "S6") (pin "4") (pinfunction "4_4") (pintype "passive"))
      (node (ref "U$14") (pin "17") (pinfunction "P33/MTIOC0D/TIOCD0/TMRI3/PO11/RXD6/RXD0/SMISO6/SMISO0/SSCL6/SSCL0/IRQ3-DS_17") (pintype "bidirectional"))
    )
    (net (code "149") (name "~{SW2}") (class "Default")
      (node (ref "S7") (pin "3") (pinfunction "3_3") (pintype "passive"))
      (node (ref "S7") (pin "4") (pinfunction "4_4") (pintype "passive"))
      (node (ref "U$14") (pin "18") (pinfunction "P32/TXD6/TXD0/SMOSI6/SMOSI0/SSDA6/SSDA0/IRQ3-DS_18") (pintype "bidirectional"))
    )
    (net (code "150") (name "~{SW3}{slash}TMS") (class "Default")
      (node (ref "JP2") (pin "9") (pinfunction "9_9") (pintype "passive"))
      (node (ref "S8") (pin "3") (pinfunction "3_3") (pintype "passive"))
      (node (ref "S8") (pin "4") (pinfunction "4_4") (pintype "passive"))
      (node (ref "U$14") (pin "19") (pinfunction "~{CTS1}/~{RTS1}/~{SS1}/SSLB0/IRQ1-DS_19") (pintype "bidirectional"))
    )
    (net (code "151") (name "~{SW4}{slash}TDI") (class "Default")
      (node (ref "S2") (pin "3") (pinfunction "3_3") (pintype "passive"))
      (node (ref "S2") (pin "4") (pinfunction "4_4") (pintype "passive"))
      (node (ref "U$14") (pin "20") (pinfunction "P30/RXD1/SMISO1/SSCL1/MISOB/IRQ0-DS_20") (pintype "bidirectional"))
    )
    (net (code "152") (name "~{TRST}") (class "Default")
      (node (ref "JP2") (pin "3") (pinfunction "3_3") (pintype "passive"))
      (node (ref "U$14") (pin "16") (pinfunction "~{TRST}/P34/MTIOC0A/TMCI3/PO12/~{POE2}/SCK6/SCK0/IRQ4_16") (pintype "bidirectional"))
      (node (ref "X3") (pin "1") (pinfunction "S_1") (pintype "passive"))
    )
  )
)
